# IoT_gateway_ver1A.net
KiCad netlist of a schematic drawn in EasyEDA Pro
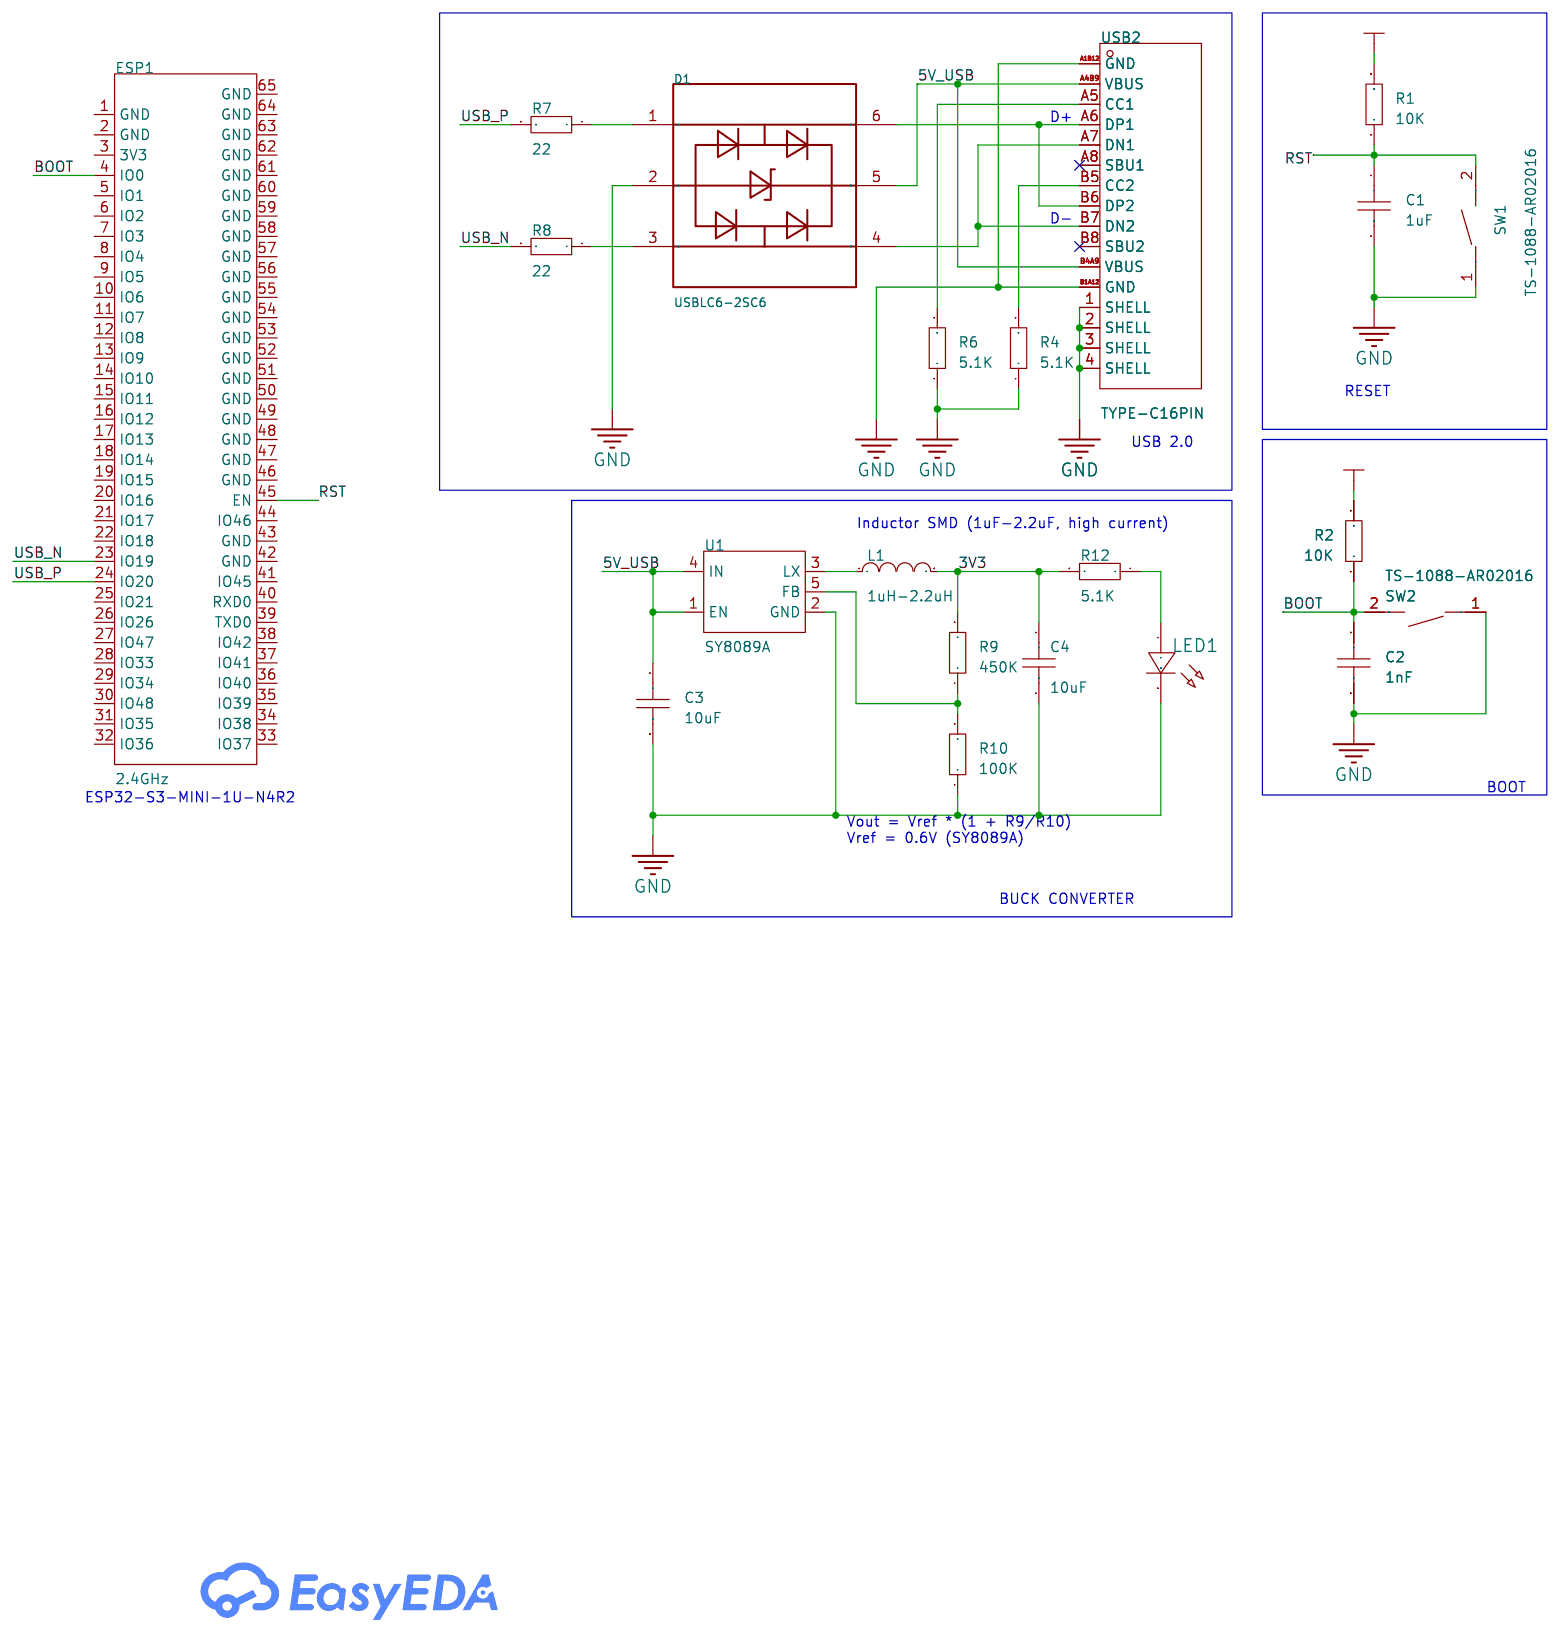
[diagram p0: ESP32-S3-Mini-1U-N4R2]
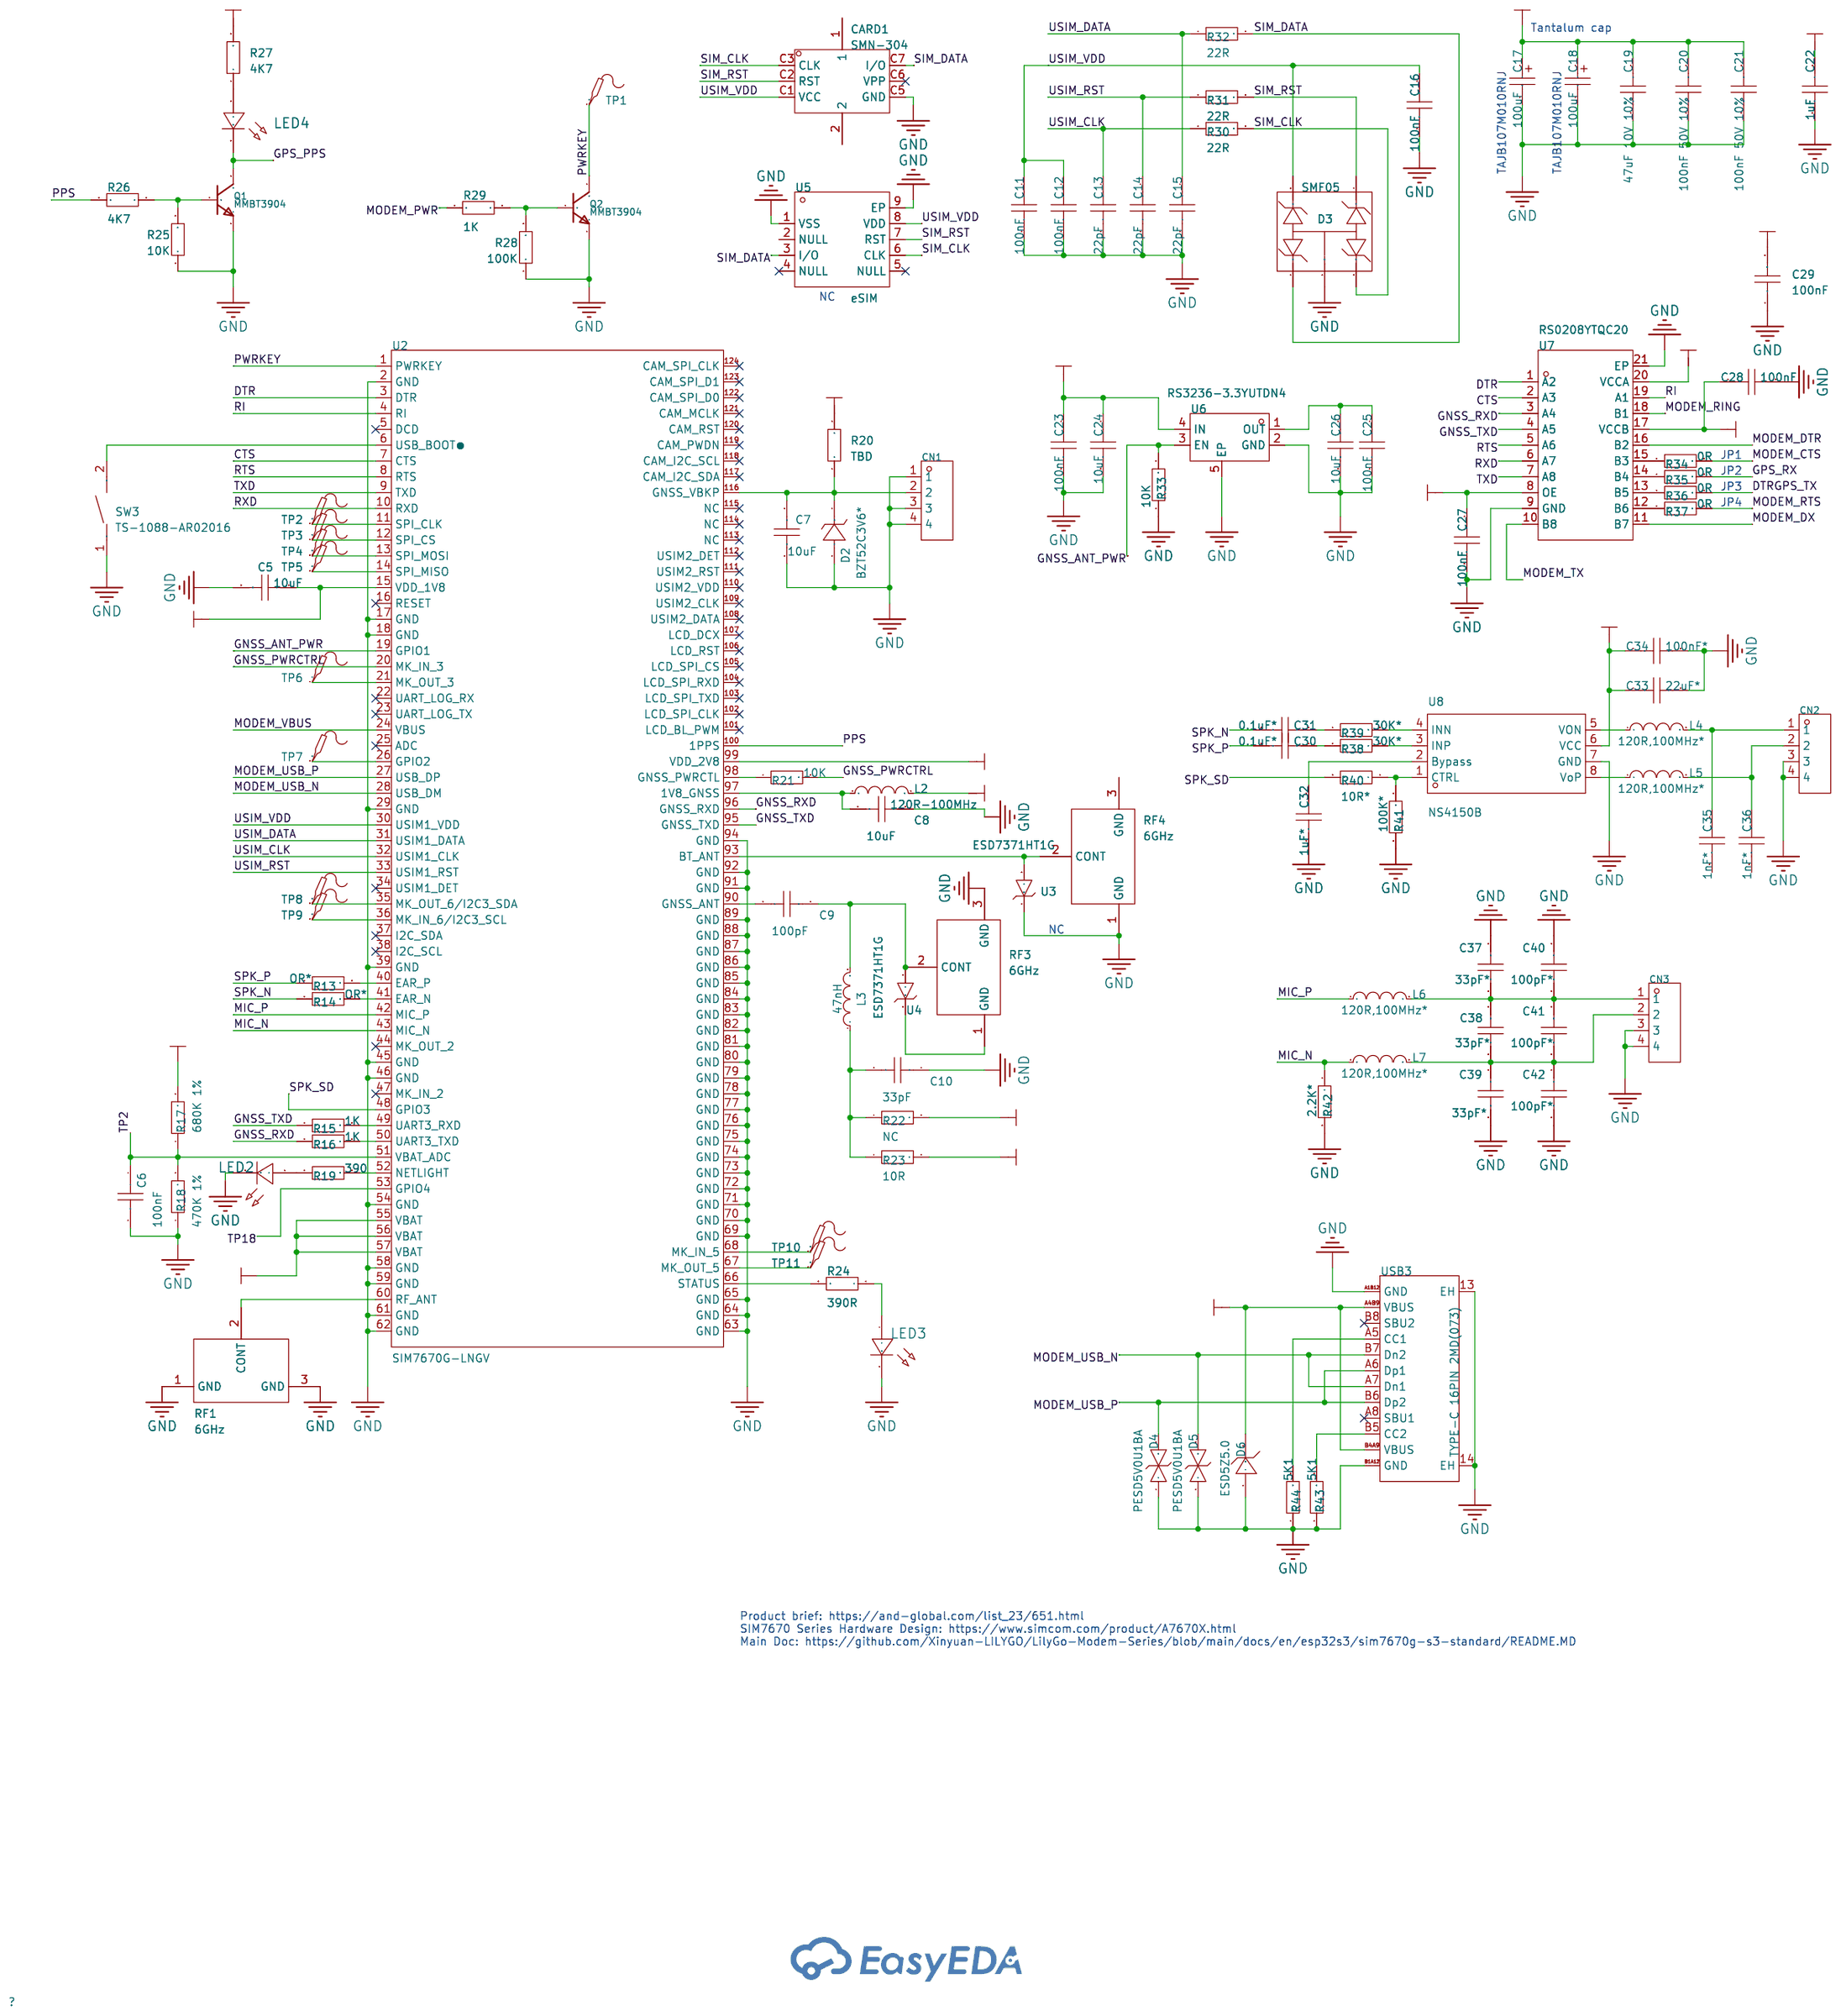
[diagram p1: SIM7670G]
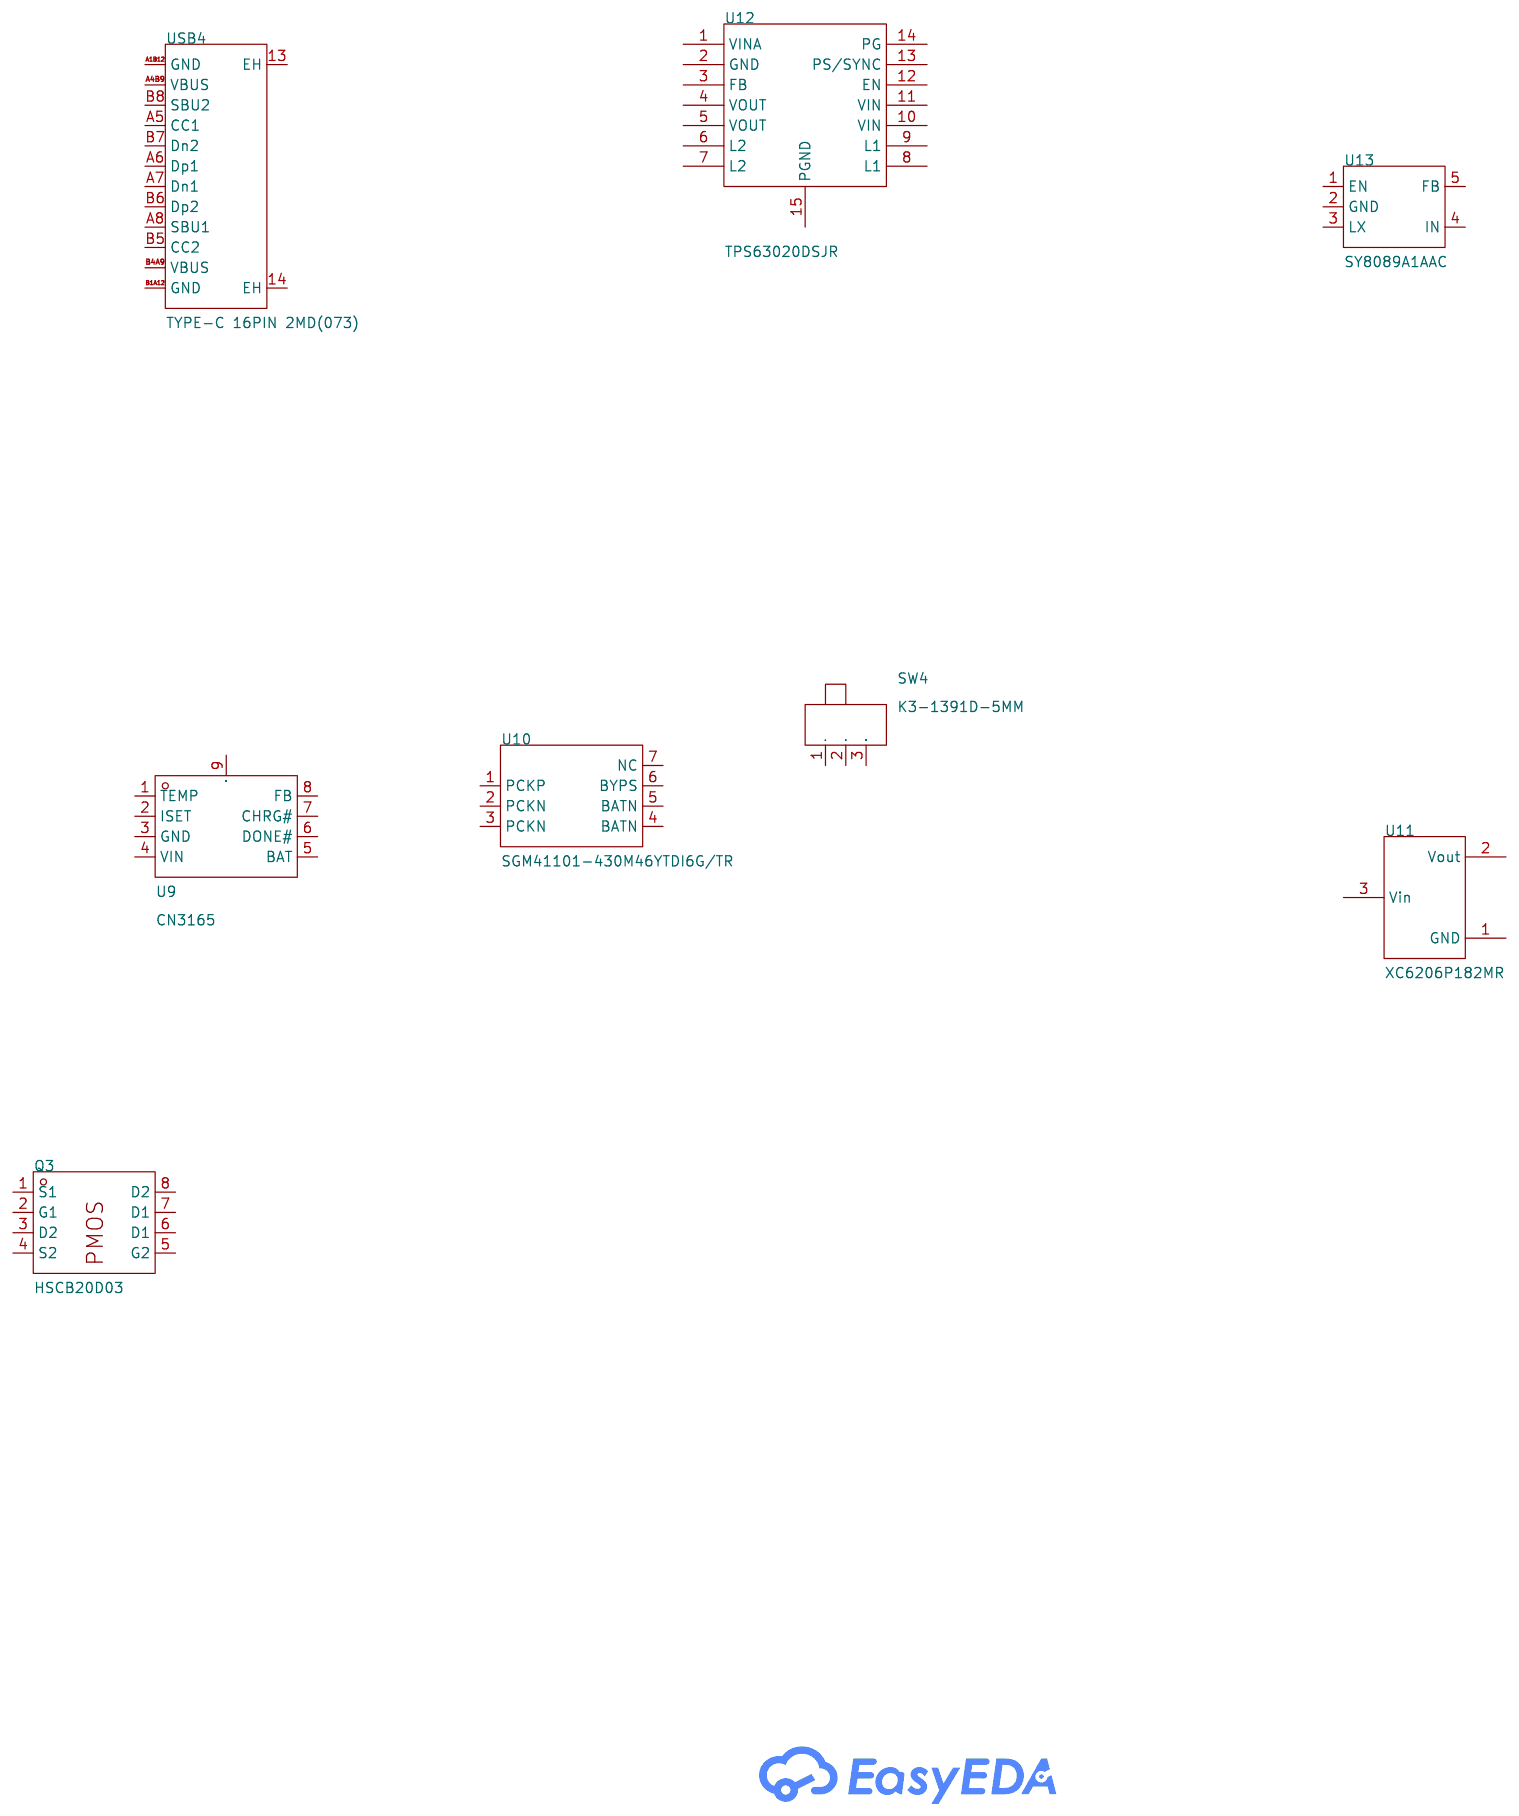
[diagram p2: Power source]
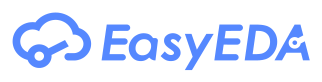
[diagram p3: SX1262]

(export (version "E")
  (design (tool "Eeschema 10.0.6"))
  (components
    (comp (ref "C1")
      (value "1uF")
      (footprint "easyedapro:C0603")
      (libsource (lib "easyedapro") (part "CAP_OLD"))
    )
    (comp (ref "C2")
      (value "1nF")
      (footprint "easyedapro:C0603")
      (libsource (lib "easyedapro") (part "CAP_OLD"))
    )
    (comp (ref "C3")
      (value "10uF")
      (footprint "easyedapro:C0603")
      (libsource (lib "easyedapro") (part "CAP_OLD"))
    )
    (comp (ref "C4")
      (value "10uF")
      (footprint "easyedapro:C0603")
      (libsource (lib "easyedapro") (part "CAP_OLD"))
    )
    (comp (ref "D1")
      (value "USBLC6-2SC6")
      (footprint "easyedapro:TSOT-23-6_L2.9-W1.6-P0.95-LS2.8-BR")
      (fields (field (name "Manufacturer") "Slkor(萨科微)"))
      (libsource (lib "easyedapro") (part "USBLC6-2SC6_C48971164"))
    )
    (comp (ref "ESP1")
      (value "2.4GHz")
      (footprint "easyedapro:BULETM-SMD_ESPRESSIF_ESP32-S3-MINI-1U-N8")
      (fields
        (field (name "Manufacturer Part") "ESP32-S3-MINI-1U-N4R2")
        (field (name "Manufacturer") "ESPRESSIF(乐鑫)")
      )
      (libsource (lib "easyedapro") (part "ESP32-S3-MINI-1U-N4R2"))
    )
    (comp (ref "L1")
      (value "1uH-2.2uH")
      (footprint "easyedapro:L0603")
      (libsource (lib "easyedapro") (part "电感"))
    )
    (comp (ref "LED1")
      (value "~")
      (footprint "easyedapro:LED0402-RD_YELLOW")
      (libsource (lib "easyedapro") (part "LED_R"))
    )
    (comp (ref "R1") (value "10K") (footprint "easyedapro:R0603") (libsource (lib "easyedapro") (part "Res")))
    (comp (ref "R2") (value "10K") (footprint "easyedapro:R0603") (libsource (lib "easyedapro") (part "Res")))
    (comp (ref "R4")
      (value "5.1K")
      (footprint "easyedapro:R0603")
      (libsource (lib "easyedapro") (part "Res"))
    )
    (comp (ref "R6")
      (value "5.1K")
      (footprint "easyedapro:R0603")
      (libsource (lib "easyedapro") (part "Res"))
    )
    (comp (ref "R7") (value "22") (footprint "easyedapro:R0603") (libsource (lib "easyedapro") (part "Res")))
    (comp (ref "R8") (value "22") (footprint "easyedapro:R0603") (libsource (lib "easyedapro") (part "Res")))
    (comp (ref "R9")
      (value "450K")
      (footprint "easyedapro:R0603")
      (libsource (lib "easyedapro") (part "Res"))
    )
    (comp (ref "R10")
      (value "100K")
      (footprint "easyedapro:R0603")
      (libsource (lib "easyedapro") (part "Res"))
    )
    (comp (ref "R12")
      (value "5.1K")
      (footprint "easyedapro:R0603")
      (libsource (lib "easyedapro") (part "Res"))
    )
    (comp (ref "SW1")
      (value "TS-1088-AR02016")
      (footprint "easyedapro:SW-SMD_L3.9-W3.0-P4.45")
      (fields (field (name "Manufacturer") "XUNPU(讯普)"))
      (libsource (lib "easyedapro") (part "TS-1088-AR02016"))
    )
    (comp (ref "SW2")
      (value "TS-1088-AR02016")
      (footprint "easyedapro:SW-SMD_L3.9-W3.0-P4.45")
      (fields (field (name "Manufacturer") "XUNPU(讯普)"))
      (libsource (lib "easyedapro") (part "TS-1088-AR02016"))
    )
    (comp (ref "U1")
      (value "SY8089A")
      (footprint "easyedapro:SOT-23-5_L3.0-W1.7-P0.95-LS2.8-BL")
      (fields (field (name "Manufacturer") "TECH PUBLIC(台舟)"))
      (libsource (lib "easyedapro") (part "SY8089A"))
    )
    (comp (ref "USB2")
      (value "TYPE-C16PIN")
      (footprint "easyedapro:USB-C-SMD_TYPE-C16PIN")
      (fields (field (name "Manufacturer") "SHOU HAN(首韩)"))
      (libsource (lib "easyedapro") (part "TYPE-C16PIN"))
    )
    (comp (ref "C5")
      (value "10uF")
      (footprint "easyedapro:C0603")
      (libsource (lib "easyedapro") (part "CAP_OLD"))
    )
    (comp (ref "C6")
      (value "100nF")
      (footprint "easyedapro:C0603")
      (libsource (lib "easyedapro") (part "CAP_OLD"))
    )
    (comp (ref "C7")
      (value "10uF")
      (footprint "easyedapro:C0603")
      (libsource (lib "easyedapro") (part "CAP_OLD"))
    )
    (comp (ref "C8")
      (value "10uF")
      (footprint "easyedapro:C0603")
      (libsource (lib "easyedapro") (part "CAP_OLD"))
    )
    (comp (ref "C9")
      (value "100pF")
      (footprint "easyedapro:C0603")
      (libsource (lib "easyedapro") (part "CAP_OLD"))
    )
    (comp (ref "C10")
      (value "33pF")
      (footprint "easyedapro:C0603")
      (libsource (lib "easyedapro") (part "CAP_OLD"))
    )
    (comp (ref "C11")
      (value "100nF")
      (footprint "easyedapro:C0603")
      (libsource (lib "easyedapro") (part "CAP_OLD"))
    )
    (comp (ref "C12")
      (value "100nF")
      (footprint "easyedapro:C0603")
      (libsource (lib "easyedapro") (part "CAP_OLD"))
    )
    (comp (ref "C13")
      (value "22pF")
      (footprint "easyedapro:C0603")
      (libsource (lib "easyedapro") (part "CAP_OLD"))
    )
    (comp (ref "C14")
      (value "22pF")
      (footprint "easyedapro:C0603")
      (libsource (lib "easyedapro") (part "CAP_OLD"))
    )
    (comp (ref "C15")
      (value "22pF")
      (footprint "easyedapro:C0603")
      (libsource (lib "easyedapro") (part "CAP_OLD"))
    )
    (comp (ref "C16")
      (value "100nF")
      (footprint "easyedapro:C0603")
      (libsource (lib "easyedapro") (part "CAP_OLD"))
    )
    (comp (ref "C17")
      (value "100uF")
      (footprint "easyedapro:CASE-B_3528")
      (fields (field (name "Manufacturer Part") "TAJB107M010RNJ") (field (name "Manufacturer") "Kyocera AVX"))
      (libsource (lib "easyedapro") (part "TAJB107M010RNJ"))
    )
    (comp (ref "C18")
      (value "100uF")
      (footprint "easyedapro:CASE-B_3528")
      (fields (field (name "Manufacturer Part") "TAJB107M010RNJ") (field (name "Manufacturer") "Kyocera AVX"))
      (libsource (lib "easyedapro") (part "TAJB107M010RNJ"))
    )
    (comp (ref "C19")
      (value "47uF 10V 10%")
      (footprint "easyedapro:C0603")
      (libsource (lib "easyedapro") (part "CAP_OLD"))
    )
    (comp (ref "C20")
      (value "100nF 50V 10%")
      (footprint "easyedapro:C0603")
      (libsource (lib "easyedapro") (part "CAP_OLD"))
    )
    (comp (ref "C21")
      (value "100nF 50V 10%")
      (footprint "easyedapro:C0603")
      (libsource (lib "easyedapro") (part "CAP_OLD"))
    )
    (comp (ref "C22")
      (value "1uF")
      (footprint "easyedapro:C0603")
      (libsource (lib "easyedapro") (part "CAP_OLD"))
    )
    (comp (ref "C23")
      (value "100nF")
      (footprint "easyedapro:C0603")
      (libsource (lib "easyedapro") (part "CAP_OLD"))
    )
    (comp (ref "C24")
      (value "10uF")
      (footprint "easyedapro:C0603")
      (libsource (lib "easyedapro") (part "CAP_OLD"))
    )
    (comp (ref "C25")
      (value "100nF")
      (footprint "easyedapro:C0603")
      (libsource (lib "easyedapro") (part "CAP_OLD"))
    )
    (comp (ref "C26")
      (value "10uF")
      (footprint "easyedapro:C0603")
      (libsource (lib "easyedapro") (part "CAP_OLD"))
    )
    (comp (ref "C27")
      (value "100nF")
      (footprint "easyedapro:C0603")
      (libsource (lib "easyedapro") (part "CAP_OLD"))
    )
    (comp (ref "C28")
      (value "100nF")
      (footprint "easyedapro:C0603")
      (libsource (lib "easyedapro") (part "CAP_OLD"))
    )
    (comp (ref "C29")
      (value "100nF")
      (footprint "easyedapro:C0603")
      (libsource (lib "easyedapro") (part "CAP_OLD"))
    )
    (comp (ref "C30")
      (value "0.1uF*")
      (footprint "easyedapro:C0603")
      (libsource (lib "easyedapro") (part "CAP_OLD"))
    )
    (comp (ref "C31")
      (value "0.1uF*")
      (footprint "easyedapro:C0603")
      (libsource (lib "easyedapro") (part "CAP_OLD"))
    )
    (comp (ref "C32")
      (value "1uF*")
      (footprint "easyedapro:C0603")
      (libsource (lib "easyedapro") (part "CAP_OLD"))
    )
    (comp (ref "C33")
      (value "22uF*")
      (footprint "easyedapro:C0603")
      (libsource (lib "easyedapro") (part "CAP_OLD"))
    )
    (comp (ref "C34")
      (value "100nF*")
      (footprint "easyedapro:C0603")
      (libsource (lib "easyedapro") (part "CAP_OLD"))
    )
    (comp (ref "C35")
      (value "1nF*")
      (footprint "easyedapro:C0603")
      (libsource (lib "easyedapro") (part "CAP_OLD"))
    )
    (comp (ref "C36")
      (value "1nF*")
      (footprint "easyedapro:C0603")
      (libsource (lib "easyedapro") (part "CAP_OLD"))
    )
    (comp (ref "C37")
      (value "33pF*")
      (footprint "easyedapro:C0603")
      (libsource (lib "easyedapro") (part "CAP_OLD"))
    )
    (comp (ref "C38")
      (value "33pF*")
      (footprint "easyedapro:C0603")
      (libsource (lib "easyedapro") (part "CAP_OLD"))
    )
    (comp (ref "C39")
      (value "33pF*")
      (footprint "easyedapro:C0603")
      (libsource (lib "easyedapro") (part "CAP_OLD"))
    )
    (comp (ref "C40")
      (value "100pF*")
      (footprint "easyedapro:C0603")
      (libsource (lib "easyedapro") (part "CAP_OLD"))
    )
    (comp (ref "C41")
      (value "100pF*")
      (footprint "easyedapro:C0603")
      (libsource (lib "easyedapro") (part "CAP_OLD"))
    )
    (comp (ref "C42")
      (value "100pF*")
      (footprint "easyedapro:C0603")
      (libsource (lib "easyedapro") (part "CAP_OLD"))
    )
    (comp (ref "CARD1")
      (value "SMN-304")
      (footprint "easyedapro:SIM-SMD_SMN-304")
      (fields (field (name "Manufacturer") "XUNPU(讯普)"))
      (libsource (lib "easyedapro") (part "SMN-304"))
    )
    (comp (ref "CN1")
      (value "~")
      (footprint "easyedapro:HDR-TH_4P-P2.54-V-F")
      (libsource (lib "easyedapro") (part "2.54-1*4P母"))
    )
    (comp (ref "CN2")
      (value "~")
      (footprint "easyedapro:HDR-TH_4P-P2.54-V-F")
      (libsource (lib "easyedapro") (part "2.54-1*4P母"))
    )
    (comp (ref "CN3")
      (value "~")
      (footprint "easyedapro:HDR-TH_4P-P2.54-V-F")
      (libsource (lib "easyedapro") (part "2.54-1*4P母"))
    )
    (comp (ref "D2")
      (value "BZT52C3V6*")
      (footprint "easyedapro:SOD-123_L2.8-W1.8-LS3.7-RD")
      (fields (field (name "Manufacturer") "PAKER(派克微)"))
      (libsource (lib "easyedapro") (part "BZT52C3V6_C49652771"))
    )
    (comp (ref "D3")
      (value "SMF05")
      (footprint "easyedapro:SOT-353_L2.0-W1.2-P0.65-LS2.1-BL-1")
      (fields (field (name "Manufacturer") "WPMtek(维攀)"))
      (libsource (lib "easyedapro") (part "SMF05"))
    )
    (comp (ref "D4")
      (value "PESD5V0U1BA")
      (footprint "easyedapro:SOD-323_L1.8-W1.3-LS2.5-BI")
      (fields (field (name "Manufacturer") "UMW(友台半导体)"))
      (libsource (lib "easyedapro") (part "PESD5V0U1BA_C5199862"))
    )
    (comp (ref "D5")
      (value "PESD5V0U1BA")
      (footprint "easyedapro:SOD-323_L1.8-W1.3-LS2.5-BI")
      (fields (field (name "Manufacturer") "UMW(友台半导体)"))
      (libsource (lib "easyedapro") (part "PESD5V0U1BA_C5199862"))
    )
    (comp (ref "D6")
      (value "ESD5Z5.0")
      (footprint "easyedapro:SOD-523_L1.2-W0.8-LS1.6-RD")
      (fields (field (name "Manufacturer") "AnBon(安邦)"))
      (libsource (lib "easyedapro") (part "ESD5Z5.0"))
    )
    (comp (ref "L2")
      (value "120R-100MHz")
      (footprint "easyedapro:L0603")
      (libsource (lib "easyedapro") (part "电感"))
    )
    (comp (ref "L3") (value "47nH") (footprint "easyedapro:L0603") (libsource (lib "easyedapro") (part "电感")))
    (comp (ref "L4")
      (value "120R,100MHz*")
      (footprint "easyedapro:L0603")
      (libsource (lib "easyedapro") (part "电感"))
    )
    (comp (ref "L5")
      (value "120R,100MHz*")
      (footprint "easyedapro:L0603")
      (libsource (lib "easyedapro") (part "电感"))
    )
    (comp (ref "L6")
      (value "120R,100MHz*")
      (footprint "easyedapro:L0603")
      (libsource (lib "easyedapro") (part "电感"))
    )
    (comp (ref "L7")
      (value "120R,100MHz*")
      (footprint "easyedapro:L0603")
      (libsource (lib "easyedapro") (part "电感"))
    )
    (comp (ref "LED2")
      (value "~")
      (footprint "easyedapro:LED0402-RD_YELLOW")
      (libsource (lib "easyedapro") (part "LED_R"))
    )
    (comp (ref "LED3")
      (value "~")
      (footprint "easyedapro:LED0402-RD_YELLOW")
      (libsource (lib "easyedapro") (part "LED_R"))
    )
    (comp (ref "LED4")
      (value "~")
      (footprint "easyedapro:LED0402-RD_YELLOW")
      (libsource (lib "easyedapro") (part "LED_R"))
    )
    (comp (ref "Q1")
      (value "MMBT3904")
      (footprint "easyedapro:SOT-23-3_L3.0-W1.7-P0.95-LS2.9-BR")
      (fields (field (name "Manufacturer") "ALJ(龙晶微)"))
      (libsource (lib "easyedapro") (part "MMBT3904_C55258612"))
    )
    (comp (ref "Q2")
      (value "MMBT3904")
      (footprint "easyedapro:SOT-23-3_L3.0-W1.7-P0.95-LS2.9-BR")
      (fields (field (name "Manufacturer") "ALJ(龙晶微)"))
      (libsource (lib "easyedapro") (part "MMBT3904_C55258612"))
    )
    (comp (ref "R13")
      (value "OR*")
      (footprint "easyedapro:R0603")
      (libsource (lib "easyedapro") (part "Res"))
    )
    (comp (ref "R14")
      (value "OR*")
      (footprint "easyedapro:R0603")
      (libsource (lib "easyedapro") (part "Res"))
    )
    (comp (ref "R15") (value "1K") (footprint "easyedapro:R0603") (libsource (lib "easyedapro") (part "Res")))
    (comp (ref "R16") (value "1K") (footprint "easyedapro:R0603") (libsource (lib "easyedapro") (part "Res")))
    (comp (ref "R17")
      (value "680K 1%")
      (footprint "easyedapro:R0603")
      (libsource (lib "easyedapro") (part "Res"))
    )
    (comp (ref "R18")
      (value "470K 1%")
      (footprint "easyedapro:R0603")
      (libsource (lib "easyedapro") (part "Res"))
    )
    (comp (ref "R19")
      (value "390")
      (footprint "easyedapro:R0603")
      (libsource (lib "easyedapro") (part "Res"))
    )
    (comp (ref "R20")
      (value "TBD")
      (footprint "easyedapro:R0603")
      (libsource (lib "easyedapro") (part "Res"))
    )
    (comp (ref "R21")
      (value "10K")
      (footprint "easyedapro:R0603")
      (libsource (lib "easyedapro") (part "Res"))
    )
    (comp (ref "R22") (value "NC") (footprint "easyedapro:R0603") (libsource (lib "easyedapro") (part "Res")))
    (comp (ref "R23")
      (value "10R")
      (footprint "easyedapro:R0603")
      (libsource (lib "easyedapro") (part "Res"))
    )
    (comp (ref "R24")
      (value "390R")
      (footprint "easyedapro:R0603")
      (libsource (lib "easyedapro") (part "Res"))
    )
    (comp (ref "R25")
      (value "10K")
      (footprint "easyedapro:R0603")
      (libsource (lib "easyedapro") (part "Res"))
    )
    (comp (ref "R26")
      (value "4K7")
      (footprint "easyedapro:R0603")
      (libsource (lib "easyedapro") (part "Res"))
    )
    (comp (ref "R27")
      (value "4K7")
      (footprint "easyedapro:R0603")
      (libsource (lib "easyedapro") (part "Res"))
    )
    (comp (ref "R28")
      (value "100K")
      (footprint "easyedapro:R0603")
      (libsource (lib "easyedapro") (part "Res"))
    )
    (comp (ref "R29") (value "1K") (footprint "easyedapro:R0603") (libsource (lib "easyedapro") (part "Res")))
    (comp (ref "R30")
      (value "22R")
      (footprint "easyedapro:R0603")
      (libsource (lib "easyedapro") (part "Res"))
    )
    (comp (ref "R31")
      (value "22R")
      (footprint "easyedapro:R0603")
      (libsource (lib "easyedapro") (part "Res"))
    )
    (comp (ref "R32")
      (value "22R")
      (footprint "easyedapro:R0603")
      (libsource (lib "easyedapro") (part "Res"))
    )
    (comp (ref "R33")
      (value "10K")
      (footprint "easyedapro:R0603")
      (libsource (lib "easyedapro") (part "Res"))
    )
    (comp (ref "R34") (value "0R") (footprint "easyedapro:R0603") (libsource (lib "easyedapro") (part "Res")))
    (comp (ref "R35") (value "0R") (footprint "easyedapro:R0603") (libsource (lib "easyedapro") (part "Res")))
    (comp (ref "R36") (value "0R") (footprint "easyedapro:R0603") (libsource (lib "easyedapro") (part "Res")))
    (comp (ref "R37") (value "0R") (footprint "easyedapro:R0603") (libsource (lib "easyedapro") (part "Res")))
    (comp (ref "R38")
      (value "30K*")
      (footprint "easyedapro:R0603")
      (libsource (lib "easyedapro") (part "Res"))
    )
    (comp (ref "R39")
      (value "30K*")
      (footprint "easyedapro:R0603")
      (libsource (lib "easyedapro") (part "Res"))
    )
    (comp (ref "R40")
      (value "10R*")
      (footprint "easyedapro:R0603")
      (libsource (lib "easyedapro") (part "Res"))
    )
    (comp (ref "R41")
      (value "100K*")
      (footprint "easyedapro:R0603")
      (libsource (lib "easyedapro") (part "Res"))
    )
    (comp (ref "R42")
      (value "2.2K*")
      (footprint "easyedapro:R0603")
      (libsource (lib "easyedapro") (part "Res"))
    )
    (comp (ref "R43")
      (value "5K1")
      (footprint "easyedapro:R0603")
      (libsource (lib "easyedapro") (part "Res"))
    )
    (comp (ref "R44")
      (value "5K1")
      (footprint "easyedapro:R0603")
      (libsource (lib "easyedapro") (part "Res"))
    )
    (comp (ref "RF1")
      (value "6GHz")
      (footprint "easyedapro:ANT-SMD_UFL-R-SMT01")
      (fields (field (name "Manufacturer Part") "U.FL-R-SMT(01)") (field (name "Manufacturer") "HRS(广濑)"))
      (libsource (lib "easyedapro") (part "U.FL-R-SMT(01)"))
    )
    (comp (ref "RF3")
      (value "6GHz")
      (footprint "easyedapro:ANT-SMD_UFL-R-SMT01")
      (fields (field (name "Manufacturer Part") "U.FL-R-SMT(01)") (field (name "Manufacturer") "HRS(广濑)"))
      (libsource (lib "easyedapro") (part "U.FL-R-SMT(01)"))
    )
    (comp (ref "RF4")
      (value "6GHz")
      (footprint "easyedapro:ANT-SMD_UFL-R-SMT01")
      (fields (field (name "Manufacturer Part") "U.FL-R-SMT(01)") (field (name "Manufacturer") "HRS(广濑)"))
      (libsource (lib "easyedapro") (part "U.FL-R-SMT(01)"))
    )
    (comp (ref "SW3")
      (value "TS-1088-AR02016")
      (footprint "easyedapro:SW-SMD_L3.9-W3.0-P4.45")
      (fields (field (name "Manufacturer") "XUNPU(讯普)"))
      (libsource (lib "easyedapro") (part "TS-1088-AR02016"))
    )
    (comp (ref "TP1")
      (value "~")
      (footprint "easyedapro:Test-Point-0.5mm")
      (description "Test Point 测试点")
      (libsource (lib "easyedapro") (part "Test-Point"))
    )
    (comp (ref "TP2")
      (value "~")
      (footprint "easyedapro:Test-Point-0.5mm")
      (description "Test Point 测试点")
      (libsource (lib "easyedapro") (part "Test-Point"))
    )
    (comp (ref "TP3")
      (value "~")
      (footprint "easyedapro:Test-Point-0.5mm")
      (description "Test Point 测试点")
      (libsource (lib "easyedapro") (part "Test-Point"))
    )
    (comp (ref "TP4")
      (value "~")
      (footprint "easyedapro:Test-Point-0.5mm")
      (description "Test Point 测试点")
      (libsource (lib "easyedapro") (part "Test-Point"))
    )
    (comp (ref "TP5")
      (value "~")
      (footprint "easyedapro:Test-Point-0.5mm")
      (description "Test Point 测试点")
      (libsource (lib "easyedapro") (part "Test-Point"))
    )
    (comp (ref "TP6")
      (value "~")
      (footprint "easyedapro:Test-Point-0.5mm")
      (description "Test Point 测试点")
      (libsource (lib "easyedapro") (part "Test-Point"))
    )
    (comp (ref "TP7")
      (value "~")
      (footprint "easyedapro:Test-Point-0.5mm")
      (description "Test Point 测试点")
      (libsource (lib "easyedapro") (part "Test-Point"))
    )
    (comp (ref "TP8")
      (value "~")
      (footprint "easyedapro:Test-Point-0.5mm")
      (description "Test Point 测试点")
      (libsource (lib "easyedapro") (part "Test-Point"))
    )
    (comp (ref "TP9")
      (value "~")
      (footprint "easyedapro:Test-Point-0.5mm")
      (description "Test Point 测试点")
      (libsource (lib "easyedapro") (part "Test-Point"))
    )
    (comp (ref "TP10")
      (value "~")
      (footprint "easyedapro:Test-Point-0.5mm")
      (description "Test Point 测试点")
      (libsource (lib "easyedapro") (part "Test-Point"))
    )
    (comp (ref "TP11")
      (value "~")
      (footprint "easyedapro:Test-Point-0.5mm")
      (description "Test Point 测试点")
      (libsource (lib "easyedapro") (part "Test-Point"))
    )
    (comp (ref "U2")
      (value "SIM7670G-LNGV")
      (footprint "easyedapro:LCC-124_L24.0-W24.0-P1.0-TL")
      (fields (field (name "Manufacturer") "SIMCOM(芯讯通无线科技)"))
      (libsource (lib "easyedapro") (part "SIM7670G-LNGV"))
    )
    (comp (ref "U3")
      (value "ESD7371HT1G")
      (footprint "easyedapro:SOD-323_L1.7-W1.3-LS2.5-RD")
      (fields (field (name "Manufacturer") "onsemi(安森美)"))
      (libsource (lib "easyedapro") (part "ESD7371HT1G"))
    )
    (comp (ref "U4")
      (value "ESD7371HT1G")
      (footprint "easyedapro:SOD-323_L1.7-W1.3-LS2.5-RD")
      (fields (field (name "Manufacturer") "onsemi(安森美)"))
      (libsource (lib "easyedapro") (part "ESD7371HT1G"))
    )
    (comp (ref "U5")
      (value "eSIM")
      (footprint "easyedapro:DFN-8_L2.0-W2.0-P0.50-LS2.0-BL-EP")
      (libsource (lib "easyedapro") (part "ESIM_C9900092443"))
    )
    (comp (ref "U6")
      (value "RS3236-3.3YUTDN4")
      (footprint "easyedapro:XDFN-4_L1.0-W1.0-P0.65-BL-EP")
      (fields (field (name "Manufacturer") "RUNIC(润石)"))
      (libsource (lib "easyedapro") (part "RS3236-3.3YUTDN4"))
    )
    (comp (ref "U7")
      (value "RS0208YTQC20")
      (footprint "easyedapro:QFN-20_L3.0-W3.0-P0.40-BL-EP1.7")
      (fields (field (name "Manufacturer") "RUNIC(润石)"))
      (libsource (lib "easyedapro") (part "RS0208YTQC20"))
    )
    (comp (ref "U8")
      (value "NS4150B")
      (footprint "easyedapro:MSOP-8_L3.0-W3.0-P0.65-LS5.0-BL")
      (description "Class:Class D Output Power:3Wx1@4Ω Voltage - Supply:3V~5.25V Voltage - Supply:3V~5.25V")
      (fields (field (name "Manufacturer") "Nsiway(纳芯威)"))
      (libsource (lib "easyedapro") (part "NS4150"))
    )
    (comp (ref "USB3")
      (value "TYPE-C 16PIN 2MD(073)")
      (footprint "easyedapro:USB-C-SMD_TYPE-C-16PIN-2MD-073")
      (fields (field (name "Manufacturer") "SHOU HAN(首韩)"))
      (libsource (lib "easyedapro") (part "TYPE-C 16PIN 2MD(073)"))
    )
    (comp (ref "Q3")
      (value "HSCB20D03")
      (footprint "easyedapro:DFN-6_L2.0-W2.0-P0.65-BL-EP2")
      (fields (field (name "Manufacturer") "HUASHUO(华朔)"))
      (libsource (lib "easyedapro") (part "HSCB20D03"))
    )
    (comp (ref "SW4")
      (value "K3-1391D-5MM")
      (footprint "easyedapro:SW-TH_K3-1391D-5MM")
      (fields (field (name "Manufacturer") "韩国韩荣"))
      (libsource (lib "easyedapro") (part "K3-1391D-5MM"))
    )
    (comp (ref "U9")
      (value "CN3165")
      (footprint "easyedapro:DFN-8_L3.0-W3.0-P0.50-BL-EP")
      (fields (field (name "Manufacturer") "CONSONANCE(上海如韵)"))
      (libsource (lib "easyedapro") (part "CN3165"))
    )
    (comp (ref "U10")
      (value "SGM41101-430M46YTDI6G/TR")
      (footprint "easyedapro:TDFN-6_L2.0-W2.0-P0.65-TL-EP1.4")
      (fields (field (name "Manufacturer") "SGMICRO(圣邦微)"))
      (libsource (lib "easyedapro") (part "SGM41101-430M46YTDI6G/TR"))
    )
    (comp (ref "U11")
      (value "XC6206P182MR")
      (footprint "easyedapro:SOT-23-3_L2.9-W1.6-P1.90-LS2.8-BR")
      (fields (field (name "Manufacturer") "TECH PUBLIC(台舟)"))
      (libsource (lib "easyedapro") (part "XC6206P182MR_C51886219"))
    )
    (comp (ref "U12")
      (value "TPS63020DSJR")
      (footprint "easyedapro:VSON-14_L4.0-W3.0-P0.50-BL-EP_TI_DSJ")
      (fields (field (name "Manufacturer") "TI(德州仪器)"))
      (libsource (lib "easyedapro") (part "TPS63020DSJR"))
    )
    (comp (ref "U13")
      (value "SY8089A1AAC")
      (footprint "easyedapro:TSOT-23-5_L2.9-W1.6-P0.95-LS2.8-BR")
      (fields (field (name "Manufacturer") "Silergy(矽力杰)"))
      (libsource (lib "easyedapro") (part "SY8089A1AAC"))
    )
    (comp (ref "USB4")
      (value "TYPE-C 16PIN 2MD(073)")
      (footprint "easyedapro:USB-C-SMD_TYPE-C-16PIN-2MD-073")
      (fields (field (name "Manufacturer") "SHOU HAN(首韩)"))
      (libsource (lib "easyedapro") (part "TYPE-C 16PIN 2MD(073)"))
    )
  )
  (nets
    (net (code "1") (name "+1.8V") (class "Default")
      (node (ref "C5") (pin "1") (pinfunction "1_1") (pintype "input"))
      (node (ref "U2") (pin "15") (pinfunction "VDD_1V8_15") (pintype "unspecified"))
    )
    (net (code "2") (name "+1V8") (class "Default")
      (node (ref "C27") (pin "1") (pinfunction "1_1") (pintype "input"))
      (node (ref "C29") (pin "2") (pinfunction "2_2") (pintype "input"))
      (node (ref "L2") (pin "2") (pinfunction "2_2") (pintype "input"))
      (node (ref "U7") (pin "20") (pinfunction "VCCA_20") (pintype "unspecified"))
      (node (ref "U7") (pin "8") (pinfunction "OE_8") (pintype "unspecified"))
    )
    (net (code "3") (name "+3V3") (class "Default")
      (node (ref "C28") (pin "1") (pinfunction "1_1") (pintype "input"))
      (node (ref "R27") (pin "2") (pinfunction "2_2") (pintype "input"))
      (node (ref "U7") (pin "17") (pinfunction "VCCB_17") (pintype "unspecified"))
    )
    (net (code "4") (name "+3V6") (class "Default")
      (node (ref "C17") (pin "1") (pinfunction "1_1") (pintype "input"))
      (node (ref "C18") (pin "1") (pinfunction "1_1") (pintype "input"))
      (node (ref "C19") (pin "1") (pinfunction "1_1") (pintype "input"))
      (node (ref "C20") (pin "1") (pinfunction "1_1") (pintype "input"))
      (node (ref "C21") (pin "1") (pinfunction "1_1") (pintype "input"))
      (node (ref "C23") (pin "1") (pinfunction "1_1") (pintype "input"))
      (node (ref "C24") (pin "1") (pinfunction "1_1") (pintype "input"))
      (node (ref "C33") (pin "1") (pinfunction "1_1") (pintype "input"))
      (node (ref "C34") (pin "1") (pinfunction "1_1") (pintype "input"))
      (node (ref "U2") (pin "55") (pinfunction "VBAT_55") (pintype "unspecified"))
      (node (ref "U2") (pin "56") (pinfunction "VBAT_56") (pintype "unspecified"))
      (node (ref "U2") (pin "57") (pinfunction "VBAT_57") (pintype "unspecified"))
      (node (ref "U6") (pin "4") (pinfunction "IN_4") (pintype "unspecified"))
      (node (ref "U8") (pin "6") (pinfunction "VCC_6") (pintype "unspecified"))
    )
    (net (code "5") (name "3.3V") (class "Default")
      (node (ref "R1") (pin "2") (pinfunction "2_2") (pintype "input"))
      (node (ref "R2") (pin "2") (pinfunction "2_2") (pintype "input"))
    )
    (net (code "6") (name "3V3") (class "Default")
      (node (ref "C4") (pin "1") (pinfunction "1_1") (pintype "input"))
      (node (ref "L1") (pin "2") (pinfunction "2_2") (pintype "input"))
      (node (ref "R12") (pin "2") (pinfunction "2_2") (pintype "input"))
      (node (ref "R9") (pin "2") (pinfunction "2_2") (pintype "input"))
    )
    (net (code "7") (name "5V_USB") (class "Default")
      (node (ref "C3") (pin "1") (pinfunction "1_1") (pintype "input"))
      (node (ref "D1") (pin "5") (pinfunction "VBUS_5") (pintype "input"))
      (node (ref "U1") (pin "1") (pinfunction "EN_1") (pintype "unspecified"))
      (node (ref "U1") (pin "4") (pinfunction "IN_4") (pintype "unspecified"))
      (node (ref "USB2") (pin "A4B9") (pinfunction "VBUS_A4B9") (pintype "unspecified"))
      (node (ref "USB2") (pin "B4A9") (pinfunction "VBUS_B4A9") (pintype "unspecified"))
    )
    (net (code "8") (name "BOOT") (class "Default")
      (node (ref "C2") (pin "1") (pinfunction "1_1") (pintype "input"))
      (node (ref "ESP1") (pin "4") (pinfunction "IO0_4") (pintype "unspecified"))
      (node (ref "R2") (pin "1") (pinfunction "1_1") (pintype "input"))
      (node (ref "SW2") (pin "2") (pinfunction "2_2") (pintype "unspecified"))
    )
    (net (code "9") (name "CTS") (class "Default")
      (node (ref "U2") (pin "7") (pinfunction "CTS_7") (pintype "unspecified"))
      (node (ref "U7") (pin "2") (pinfunction "A3_2") (pintype "unspecified"))
    )
    (net (code "10") (name "DTR") (class "Default")
      (node (ref "U2") (pin "3") (pinfunction "DTR_3") (pintype "unspecified"))
      (node (ref "U7") (pin "1") (pinfunction "A2_1") (pintype "unspecified"))
    )
    (net (code "11") (name "DTRGPS_TX") (class "Default")
      (node (ref "R36") (pin "2") (pinfunction "2_2") (pintype "input"))
    )
    (net (code "12") (name "GND") (class "Default")
      (node (ref "C1") (pin "2") (pinfunction "2_2") (pintype "input"))
      (node (ref "C10") (pin "1") (pinfunction "1_1") (pintype "input"))
      (node (ref "C11") (pin "2") (pinfunction "2_2") (pintype "input"))
      (node (ref "C12") (pin "2") (pinfunction "2_2") (pintype "input"))
      (node (ref "C13") (pin "2") (pinfunction "2_2") (pintype "input"))
      (node (ref "C14") (pin "2") (pinfunction "2_2") (pintype "input"))
      (node (ref "C15") (pin "2") (pinfunction "2_2") (pintype "input"))
      (node (ref "C16") (pin "2") (pinfunction "2_2") (pintype "input"))
      (node (ref "C17") (pin "2") (pinfunction "2_2") (pintype "input"))
      (node (ref "C18") (pin "2") (pinfunction "2_2") (pintype "input"))
      (node (ref "C19") (pin "2") (pinfunction "2_2") (pintype "input"))
      (node (ref "C2") (pin "2") (pinfunction "2_2") (pintype "input"))
      (node (ref "C20") (pin "2") (pinfunction "2_2") (pintype "input"))
      (node (ref "C21") (pin "2") (pinfunction "2_2") (pintype "input"))
      (node (ref "C22") (pin "2") (pinfunction "2_2") (pintype "input"))
      (node (ref "C23") (pin "2") (pinfunction "2_2") (pintype "input"))
      (node (ref "C24") (pin "2") (pinfunction "2_2") (pintype "input"))
      (node (ref "C25") (pin "2") (pinfunction "2_2") (pintype "input"))
      (node (ref "C26") (pin "2") (pinfunction "2_2") (pintype "input"))
      (node (ref "C27") (pin "2") (pinfunction "2_2") (pintype "input"))
      (node (ref "C28") (pin "2") (pinfunction "2_2") (pintype "input"))
      (node (ref "C29") (pin "1") (pinfunction "1_1") (pintype "input"))
      (node (ref "C3") (pin "2") (pinfunction "2_2") (pintype "input"))
      (node (ref "C32") (pin "2") (pinfunction "2_2") (pintype "input"))
      (node (ref "C33") (pin "2") (pinfunction "2_2") (pintype "input"))
      (node (ref "C34") (pin "2") (pinfunction "2_2") (pintype "input"))
      (node (ref "C37") (pin "1") (pinfunction "1_1") (pintype "input"))
      (node (ref "C39") (pin "2") (pinfunction "2_2") (pintype "input"))
      (node (ref "C4") (pin "2") (pinfunction "2_2") (pintype "input"))
      (node (ref "C40") (pin "1") (pinfunction "1_1") (pintype "input"))
      (node (ref "C42") (pin "2") (pinfunction "2_2") (pintype "input"))
      (node (ref "C5") (pin "2") (pinfunction "2_2") (pintype "input"))
      (node (ref "C6") (pin "2") (pinfunction "2_2") (pintype "input"))
      (node (ref "C7") (pin "2") (pinfunction "2_2") (pintype "input"))
      (node (ref "C8") (pin "1") (pinfunction "1_1") (pintype "input"))
      (node (ref "CARD1") (pin "C5") (pinfunction "GND_C5") (pintype "unspecified"))
      (node (ref "CN1") (pin "1") (pinfunction "1_1") (pintype "input"))
      (node (ref "CN1") (pin "3") (pinfunction "3_3") (pintype "input"))
      (node (ref "CN1") (pin "4") (pinfunction "4_4") (pintype "input"))
      (node (ref "CN2") (pin "3") (pinfunction "3_3") (pintype "input"))
      (node (ref "CN2") (pin "4") (pinfunction "4_4") (pintype "input"))
      (node (ref "CN3") (pin "3") (pinfunction "3_3") (pintype "input"))
      (node (ref "CN3") (pin "4") (pinfunction "4_4") (pintype "input"))
      (node (ref "D1") (pin "2") (pinfunction "GND_2") (pintype "input"))
      (node (ref "D2") (pin "2") (pinfunction "A_2") (pintype "unspecified"))
      (node (ref "D3") (pin "2") (pinfunction "2_2") (pintype "unspecified"))
      (node (ref "D4") (pin "1") (pinfunction "1_1") (pintype "unspecified"))
      (node (ref "D5") (pin "1") (pinfunction "1_1") (pintype "unspecified"))
      (node (ref "D6") (pin "2") (pinfunction "A_2") (pintype "unspecified"))
      (node (ref "LED1") (pin "2") (pinfunction "C_2") (pintype "input"))
      (node (ref "LED2") (pin "2") (pinfunction "C_2") (pintype "input"))
      (node (ref "LED3") (pin "2") (pinfunction "C_2") (pintype "input"))
      (node (ref "Q1") (pin "2") (pinfunction "E_2") (pintype "input"))
      (node (ref "Q2") (pin "2") (pinfunction "E_2") (pintype "input"))
      (node (ref "R10") (pin "1") (pinfunction "1_1") (pintype "input"))
      (node (ref "R18") (pin "1") (pinfunction "1_1") (pintype "input"))
      (node (ref "R25") (pin "1") (pinfunction "1_1") (pintype "input"))
      (node (ref "R28") (pin "1") (pinfunction "1_1") (pintype "input"))
      (node (ref "R33") (pin "1") (pinfunction "1_1") (pintype "input"))
      (node (ref "R4") (pin "1") (pinfunction "1_1") (pintype "input"))
      (node (ref "R41") (pin "2") (pinfunction "2_2") (pintype "input"))
      (node (ref "R42") (pin "2") (pinfunction "2_2") (pintype "input"))
      (node (ref "R43") (pin "1") (pinfunction "1_1") (pintype "input"))
      (node (ref "R44") (pin "1") (pinfunction "1_1") (pintype "input"))
      (node (ref "R6") (pin "1") (pinfunction "1_1") (pintype "input"))
      (node (ref "RF1") (pin "1") (pinfunction "GND_1") (pintype "unspecified"))
      (node (ref "RF1") (pin "3") (pinfunction "GND_3") (pintype "unspecified"))
      (node (ref "RF3") (pin "3") (pinfunction "GND_3") (pintype "unspecified"))
      (node (ref "RF4") (pin "1") (pinfunction "GND_1") (pintype "unspecified"))
      (node (ref "SW1") (pin "1") (pinfunction "1_1") (pintype "unspecified"))
      (node (ref "SW2") (pin "1") (pinfunction "1_1") (pintype "unspecified"))
      (node (ref "SW3") (pin "1") (pinfunction "1_1") (pintype "unspecified"))
      (node (ref "U1") (pin "2") (pinfunction "GND_2") (pintype "unspecified"))
      (node (ref "U2") (pin "17") (pinfunction "GND_17") (pintype "unspecified"))
      (node (ref "U2") (pin "18") (pinfunction "GND_18") (pintype "unspecified"))
      (node (ref "U2") (pin "2") (pinfunction "GND_2") (pintype "unspecified"))
      (node (ref "U2") (pin "29") (pinfunction "GND_29") (pintype "unspecified"))
      (node (ref "U2") (pin "39") (pinfunction "GND_39") (pintype "unspecified"))
      (node (ref "U2") (pin "45") (pinfunction "GND_45") (pintype "unspecified"))
      (node (ref "U2") (pin "46") (pinfunction "GND_46") (pintype "unspecified"))
      (node (ref "U2") (pin "54") (pinfunction "GND_54") (pintype "unspecified"))
      (node (ref "U2") (pin "58") (pinfunction "GND_58") (pintype "unspecified"))
      (node (ref "U2") (pin "59") (pinfunction "GND_59") (pintype "unspecified"))
      (node (ref "U2") (pin "61") (pinfunction "GND_61") (pintype "unspecified"))
      (node (ref "U2") (pin "62") (pinfunction "GND_62") (pintype "unspecified"))
      (node (ref "U2") (pin "63") (pinfunction "GND_63") (pintype "unspecified"))
      (node (ref "U2") (pin "64") (pinfunction "GND_64") (pintype "unspecified"))
      (node (ref "U2") (pin "65") (pinfunction "GND_65") (pintype "unspecified"))
      (node (ref "U2") (pin "69") (pinfunction "GND_69") (pintype "unspecified"))
      (node (ref "U2") (pin "70") (pinfunction "GND_70") (pintype "unspecified"))
      (node (ref "U2") (pin "71") (pinfunction "GND_71") (pintype "unspecified"))
      (node (ref "U2") (pin "72") (pinfunction "GND_72") (pintype "unspecified"))
      (node (ref "U2") (pin "73") (pinfunction "GND_73") (pintype "unspecified"))
      (node (ref "U2") (pin "74") (pinfunction "GND_74") (pintype "unspecified"))
      (node (ref "U2") (pin "75") (pinfunction "GND_75") (pintype "unspecified"))
      (node (ref "U2") (pin "76") (pinfunction "GND_76") (pintype "unspecified"))
      (node (ref "U2") (pin "77") (pinfunction "GND_77") (pintype "unspecified"))
      (node (ref "U2") (pin "78") (pinfunction "GND_78") (pintype "unspecified"))
      (node (ref "U2") (pin "79") (pinfunction "GND_79") (pintype "unspecified"))
      (node (ref "U2") (pin "80") (pinfunction "GND_80") (pintype "unspecified"))
      (node (ref "U2") (pin "81") (pinfunction "GND_81") (pintype "unspecified"))
      (node (ref "U2") (pin "82") (pinfunction "GND_82") (pintype "unspecified"))
      (node (ref "U2") (pin "83") (pinfunction "GND_83") (pintype "unspecified"))
      (node (ref "U2") (pin "84") (pinfunction "GND_84") (pintype "unspecified"))
      (node (ref "U2") (pin "85") (pinfunction "GND_85") (pintype "unspecified"))
      (node (ref "U2") (pin "86") (pinfunction "GND_86") (pintype "unspecified"))
      (node (ref "U2") (pin "87") (pinfunction "GND_87") (pintype "unspecified"))
      (node (ref "U2") (pin "88") (pinfunction "GND_88") (pintype "unspecified"))
      (node (ref "U2") (pin "89") (pinfunction "GND_89") (pintype "unspecified"))
      (node (ref "U2") (pin "91") (pinfunction "GND_91") (pintype "unspecified"))
      (node (ref "U2") (pin "92") (pinfunction "GND_92") (pintype "unspecified"))
      (node (ref "U2") (pin "94") (pinfunction "GND_94") (pintype "unspecified"))
      (node (ref "U3") (pin "1") (pinfunction "C_1") (pintype "unspecified"))
      (node (ref "U5") (pin "1") (pinfunction "VSS_1") (pintype "unspecified"))
      (node (ref "U5") (pin "9") (pinfunction "EP_9") (pintype "unspecified"))
      (node (ref "U6") (pin "2") (pinfunction "GND_2") (pintype "unspecified"))
      (node (ref "U6") (pin "5") (pinfunction "EP_5") (pintype "unspecified"))
      (node (ref "U7") (pin "21") (pinfunction "EP_21") (pintype "unspecified"))
      (node (ref "U7") (pin "9") (pinfunction "GND_9") (pintype "unspecified"))
      (node (ref "U8") (pin "7") (pinfunction "GND_7") (pintype "unspecified"))
      (node (ref "USB2") (pin "1") (pinfunction "SHELL_1") (pintype "unspecified"))
      (node (ref "USB2") (pin "2") (pinfunction "SHELL_2") (pintype "unspecified"))
      (node (ref "USB2") (pin "3") (pinfunction "SHELL_3") (pintype "unspecified"))
      (node (ref "USB2") (pin "4") (pinfunction "SHELL_4") (pintype "unspecified"))
      (node (ref "USB2") (pin "A1B12") (pinfunction "GND_A1B12") (pintype "unspecified"))
      (node (ref "USB2") (pin "B1A12") (pinfunction "GND_B1A12") (pintype "unspecified"))
      (node (ref "USB3") (pin "13") (pinfunction "EH_13") (pintype "unspecified"))
      (node (ref "USB3") (pin "14") (pinfunction "EH_14") (pintype "unspecified"))
      (node (ref "USB3") (pin "A1B12") (pinfunction "GND_A1B12") (pintype "unspecified"))
      (node (ref "USB3") (pin "B1A12") (pinfunction "GND_B1A12") (pintype "unspecified"))
    )
    (net (code "13") (name "GNSS_ANT_PWR") (class "Default")
      (node (ref "R33") (pin "2") (pinfunction "2_2") (pintype "input"))
      (node (ref "U2") (pin "19") (pinfunction "GPIO1_19") (pintype "unspecified"))
      (node (ref "U6") (pin "3") (pinfunction "EN_3") (pintype "unspecified"))
    )
    (net (code "14") (name "GNSS_PWRCTRL") (class "Default")
      (node (ref "R21") (pin "2") (pinfunction "2_2") (pintype "input"))
      (node (ref "U2") (pin "20") (pinfunction "MK_IN_3_20") (pintype "unspecified"))
    )
    (net (code "15") (name "GNSS_RXD") (class "Default")
      (node (ref "R16") (pin "1") (pinfunction "1_1") (pintype "input"))
      (node (ref "U2") (pin "96") (pinfunction "GNSS_RXD_96") (pintype "unspecified"))
      (node (ref "U7") (pin "3") (pinfunction "A4_3") (pintype "unspecified"))
    )
    (net (code "16") (name "GNSS_TXD") (class "Default")
      (node (ref "R15") (pin "1") (pinfunction "1_1") (pintype "input"))
      (node (ref "U2") (pin "95") (pinfunction "GNSS_TXD_95") (pintype "unspecified"))
      (node (ref "U7") (pin "4") (pinfunction "A5_4") (pintype "unspecified"))
    )
    (net (code "17") (name "GPS_PPS") (class "Default")
      (node (ref "LED4") (pin "2") (pinfunction "C_2") (pintype "input"))
      (node (ref "Q1") (pin "3") (pinfunction "C_3") (pintype "input"))
    )
    (net (code "18") (name "GPS_RX") (class "Default")
      (node (ref "R35") (pin "2") (pinfunction "2_2") (pintype "input"))
    )
    (net (code "19") (name "MIC_N") (class "Default")
      (node (ref "L7") (pin "1") (pinfunction "1_1") (pintype "input"))
      (node (ref "R42") (pin "1") (pinfunction "1_1") (pintype "input"))
      (node (ref "U2") (pin "43") (pinfunction "MIC_N_43") (pintype "unspecified"))
    )
    (net (code "20") (name "MIC_P") (class "Default")
      (node (ref "L6") (pin "1") (pinfunction "1_1") (pintype "input"))
      (node (ref "U2") (pin "42") (pinfunction "MIC_P_42") (pintype "unspecified"))
    )
    (net (code "21") (name "MODEM_CTS") (class "Default")
      (node (ref "R34") (pin "2") (pinfunction "2_2") (pintype "input"))
    )
    (net (code "22") (name "MODEM_DTR") (class "Default")
      (node (ref "U7") (pin "16") (pinfunction "B2_16") (pintype "unspecified"))
    )
    (net (code "23") (name "MODEM_DX") (class "Default")
      (node (ref "U7") (pin "11") (pinfunction "B7_11") (pintype "unspecified"))
    )
    (net (code "24") (name "MODEM_PWR") (class "Default")
      (node (ref "R29") (pin "2") (pinfunction "2_2") (pintype "input"))
    )
    (net (code "25") (name "MODEM_RING") (class "Default")
      (node (ref "U7") (pin "18") (pinfunction "B1_18") (pintype "unspecified"))
    )
    (net (code "26") (name "MODEM_RTS") (class "Default")
      (node (ref "R37") (pin "2") (pinfunction "2_2") (pintype "input"))
    )
    (net (code "27") (name "MODEM_TX") (class "Default")
      (node (ref "U7") (pin "10") (pinfunction "B8_10") (pintype "unspecified"))
    )
    (net (code "28") (name "MODEM_USB_N") (class "Default")
      (node (ref "D5") (pin "2") (pinfunction "2_2") (pintype "unspecified"))
      (node (ref "U2") (pin "28") (pinfunction "USB_DM_28") (pintype "unspecified"))
      (node (ref "USB3") (pin "A7") (pinfunction "Dn1_A7") (pintype "unspecified"))
      (node (ref "USB3") (pin "B7") (pinfunction "Dn2_B7") (pintype "unspecified"))
    )
    (net (code "29") (name "MODEM_USB_P") (class "Default")
      (node (ref "D4") (pin "2") (pinfunction "2_2") (pintype "unspecified"))
      (node (ref "U2") (pin "27") (pinfunction "USB_DP_27") (pintype "unspecified"))
      (node (ref "USB3") (pin "A6") (pinfunction "Dp1_A6") (pintype "unspecified"))
      (node (ref "USB3") (pin "B6") (pinfunction "Dp2_B6") (pintype "unspecified"))
    )
    (net (code "30") (name "MODEM_VBUS") (class "Default")
      (node (ref "D6") (pin "1") (pinfunction "C_1") (pintype "unspecified"))
      (node (ref "U2") (pin "24") (pinfunction "VBUS_24") (pintype "unspecified"))
      (node (ref "USB3") (pin "A4B9") (pinfunction "VBUS_A4B9") (pintype "unspecified"))
      (node (ref "USB3") (pin "B4A9") (pinfunction "VBUS_B4A9") (pintype "unspecified"))
    )
    (net (code "31") (name "Net-(C10-Pad2)") (class "Default")
      (node (ref "C10") (pin "2") (pinfunction "2_2") (pintype "input"))
      (node (ref "L3") (pin "1") (pinfunction "1_1") (pintype "input"))
      (node (ref "R22") (pin "1") (pinfunction "1_1") (pintype "input"))
      (node (ref "R23") (pin "1") (pinfunction "1_1") (pintype "input"))
    )
    (net (code "32") (name "Net-(C30-Pad1)") (class "Default")
      (node (ref "C30") (pin "1") (pinfunction "1_1") (pintype "input"))
      (node (ref "R38") (pin "1") (pinfunction "1_1") (pintype "input"))
    )
    (net (code "33") (name "Net-(C31-Pad1)") (class "Default")
      (node (ref "C31") (pin "1") (pinfunction "1_1") (pintype "input"))
      (node (ref "R39") (pin "1") (pinfunction "1_1") (pintype "input"))
    )
    (net (code "34") (name "Net-(C35-Pad1)") (class "Default")
      (node (ref "C35") (pin "1") (pinfunction "1_1") (pintype "input"))
      (node (ref "CN2") (pin "1") (pinfunction "1_1") (pintype "input"))
      (node (ref "L4") (pin "2") (pinfunction "2_2") (pintype "input"))
    )
    (net (code "35") (name "Net-(C36-Pad1)") (class "Default")
      (node (ref "C36") (pin "1") (pinfunction "1_1") (pintype "input"))
      (node (ref "CN2") (pin "2") (pinfunction "2_2") (pintype "input"))
      (node (ref "L5") (pin "2") (pinfunction "2_2") (pintype "input"))
    )
    (net (code "36") (name "Net-(C37-Pad2)") (class "Default")
      (node (ref "C37") (pin "2") (pinfunction "2_2") (pintype "input"))
      (node (ref "C38") (pin "1") (pinfunction "1_1") (pintype "input"))
      (node (ref "C40") (pin "2") (pinfunction "2_2") (pintype "input"))
      (node (ref "C41") (pin "1") (pinfunction "1_1") (pintype "input"))
      (node (ref "CN3") (pin "1") (pinfunction "1_1") (pintype "input"))
      (node (ref "L6") (pin "2") (pinfunction "2_2") (pintype "input"))
    )
    (net (code "37") (name "Net-(C38-Pad2)") (class "Default")
      (node (ref "C38") (pin "2") (pinfunction "2_2") (pintype "input"))
      (node (ref "C39") (pin "1") (pinfunction "1_1") (pintype "input"))
      (node (ref "C41") (pin "2") (pinfunction "2_2") (pintype "input"))
      (node (ref "C42") (pin "1") (pinfunction "1_1") (pintype "input"))
      (node (ref "CN3") (pin "2") (pinfunction "2_2") (pintype "input"))
      (node (ref "L7") (pin "2") (pinfunction "2_2") (pintype "input"))
    )
    (net (code "38") (name "Net-(D1-I{slash}O1-Pad1)") (class "Default")
      (node (ref "D1") (pin "1") (pinfunction "I/O1_1") (pintype "input"))
      (node (ref "R7") (pin "1") (pinfunction "1_1") (pintype "input"))
    )
    (net (code "39") (name "Net-(D1-I{slash}O2-Pad3)") (class "Default")
      (node (ref "D1") (pin "3") (pinfunction "I/O2_3") (pintype "input"))
      (node (ref "R8") (pin "1") (pinfunction "1_1") (pintype "input"))
    )
    (net (code "40") (name "Net-(D2-C)") (class "Default")
      (node (ref "C7") (pin "1") (pinfunction "1_1") (pintype "input"))
      (node (ref "CN1") (pin "2") (pinfunction "2_2") (pintype "input"))
      (node (ref "D2") (pin "1") (pinfunction "C_1") (pintype "unspecified"))
      (node (ref "R20") (pin "1") (pinfunction "1_1") (pintype "input"))
      (node (ref "U2") (pin "116") (pinfunction "GNSS_VBKP_116") (pintype "unspecified"))
    )
    (net (code "41") (name "Net-(LED1-A)") (class "Default")
      (node (ref "LED1") (pin "1") (pinfunction "A_1") (pintype "input"))
      (node (ref "R12") (pin "1") (pinfunction "1_1") (pintype "input"))
    )
    (net (code "42") (name "Net-(LED2-A)") (class "Default")
      (node (ref "LED2") (pin "1") (pinfunction "A_1") (pintype "input"))
      (node (ref "R19") (pin "1") (pinfunction "1_1") (pintype "input"))
    )
    (net (code "43") (name "Net-(LED3-A)") (class "Default")
      (node (ref "LED3") (pin "1") (pinfunction "A_1") (pintype "input"))
      (node (ref "R24") (pin "1") (pinfunction "1_1") (pintype "input"))
    )
    (net (code "44") (name "Net-(LED4-A)") (class "Default")
      (node (ref "LED4") (pin "1") (pinfunction "A_1") (pintype "input"))
      (node (ref "R27") (pin "1") (pinfunction "1_1") (pintype "input"))
    )
    (net (code "45") (name "Net-(Q1-B)") (class "Default")
      (node (ref "Q1") (pin "1") (pinfunction "B_1") (pintype "input"))
      (node (ref "R25") (pin "2") (pinfunction "2_2") (pintype "input"))
      (node (ref "R26") (pin "1") (pinfunction "1_1") (pintype "input"))
    )
    (net (code "46") (name "Net-(Q2-B)") (class "Default")
      (node (ref "Q2") (pin "1") (pinfunction "B_1") (pintype "input"))
      (node (ref "R28") (pin "2") (pinfunction "2_2") (pintype "input"))
      (node (ref "R29") (pin "1") (pinfunction "1_1") (pintype "input"))
    )
    (net (code "47") (name "Net-(RF1-CONT)") (class "Default")
      (node (ref "RF1") (pin "2") (pinfunction "CONT_2") (pintype "unspecified"))
      (node (ref "U2") (pin "60") (pinfunction "RF_ANT_60") (pintype "unspecified"))
    )
    (net (code "48") (name "Net-(RF3-CONT)") (class "Default")
      (node (ref "C9") (pin "1") (pinfunction "1_1") (pintype "input"))
      (node (ref "L3") (pin "2") (pinfunction "2_2") (pintype "input"))
      (node (ref "RF3") (pin "2") (pinfunction "CONT_2") (pintype "unspecified"))
      (node (ref "U4") (pin "2") (pinfunction "A_2") (pintype "unspecified"))
    )
    (net (code "49") (name "Net-(RF4-CONT)") (class "Default")
      (node (ref "RF4") (pin "2") (pinfunction "CONT_2") (pintype "unspecified"))
      (node (ref "U2") (pin "93") (pinfunction "BT_ANT_93") (pintype "unspecified"))
      (node (ref "U3") (pin "2") (pinfunction "A_2") (pintype "unspecified"))
    )
    (net (code "50") (name "Net-(U1-FB)") (class "Default")
      (node (ref "R10") (pin "2") (pinfunction "2_2") (pintype "input"))
      (node (ref "R9") (pin "1") (pinfunction "1_1") (pintype "input"))
      (node (ref "U1") (pin "5") (pinfunction "FB_5") (pintype "unspecified"))
    )
    (net (code "51") (name "Net-(U1-LX)") (class "Default")
      (node (ref "L1") (pin "1") (pinfunction "1_1") (pintype "input"))
      (node (ref "U1") (pin "3") (pinfunction "LX_3") (pintype "unspecified"))
    )
    (net (code "52") (name "Net-(U2-1V8_GNSS)") (class "Default")
      (node (ref "C8") (pin "2") (pinfunction "2_2") (pintype "input"))
      (node (ref "L2") (pin "1") (pinfunction "1_1") (pintype "input"))
      (node (ref "U2") (pin "97") (pinfunction "1V8_GNSS_97") (pintype "unspecified"))
    )
    (net (code "53") (name "Net-(U2-EAR_N)") (class "Default")
      (node (ref "R14") (pin "2") (pinfunction "2_2") (pintype "input"))
      (node (ref "U2") (pin "41") (pinfunction "EAR_N_41") (pintype "unspecified"))
    )
    (net (code "54") (name "Net-(U2-EAR_P)") (class "Default")
      (node (ref "R13") (pin "2") (pinfunction "2_2") (pintype "input"))
      (node (ref "U2") (pin "40") (pinfunction "EAR_P_40") (pintype "unspecified"))
    )
    (net (code "55") (name "Net-(U2-GNSS_ANT)") (class "Default")
      (node (ref "C9") (pin "2") (pinfunction "2_2") (pintype "input"))
      (node (ref "U2") (pin "90") (pinfunction "GNSS_ANT_90") (pintype "unspecified"))
    )
    (net (code "56") (name "Net-(U2-GNSS_PWRCTL)") (class "Default")
      (node (ref "R21") (pin "1") (pinfunction "1_1") (pintype "input"))
      (node (ref "U2") (pin "98") (pinfunction "GNSS_PWRCTL_98") (pintype "unspecified"))
    )
    (net (code "57") (name "Net-(U2-GPIO2)") (class "Default")
      (node (ref "TP7") (pin "1") (pinfunction "1_1") (pintype "unspecified"))
      (node (ref "U2") (pin "26") (pinfunction "GPIO2_26") (pintype "unspecified"))
    )
    (net (code "58") (name "Net-(U2-MK_IN_5)") (class "Default")
      (node (ref "TP10") (pin "1") (pinfunction "1_1") (pintype "unspecified"))
      (node (ref "U2") (pin "68") (pinfunction "MK_IN_5_68") (pintype "unspecified"))
    )
    (net (code "59") (name "Net-(U2-MK_IN_6{slash}I2C3_SCL)") (class "Default")
      (node (ref "TP9") (pin "1") (pinfunction "1_1") (pintype "unspecified"))
      (node (ref "U2") (pin "36") (pinfunction "MK_IN_6/I2C3_SCL_36") (pintype "unspecified"))
    )
    (net (code "60") (name "Net-(U2-MK_OUT_3)") (class "Default")
      (node (ref "TP6") (pin "1") (pinfunction "1_1") (pintype "unspecified"))
      (node (ref "U2") (pin "21") (pinfunction "MK_OUT_3_21") (pintype "unspecified"))
    )
    (net (code "61") (name "Net-(U2-MK_OUT_5)") (class "Default")
      (node (ref "TP11") (pin "1") (pinfunction "1_1") (pintype "unspecified"))
      (node (ref "U2") (pin "67") (pinfunction "MK_OUT_5_67") (pintype "unspecified"))
    )
    (net (code "62") (name "Net-(U2-MK_OUT_6{slash}I2C3_SDA)") (class "Default")
      (node (ref "TP8") (pin "1") (pinfunction "1_1") (pintype "unspecified"))
      (node (ref "U2") (pin "35") (pinfunction "MK_OUT_6/I2C3_SDA_35") (pintype "unspecified"))
    )
    (net (code "63") (name "Net-(U2-NETLIGHT)") (class "Default")
      (node (ref "R19") (pin "2") (pinfunction "2_2") (pintype "input"))
      (node (ref "U2") (pin "52") (pinfunction "NETLIGHT_52") (pintype "unspecified"))
    )
    (net (code "64") (name "Net-(U2-SPI_CLK)") (class "Default")
      (node (ref "TP2") (pin "1") (pinfunction "1_1") (pintype "unspecified"))
      (node (ref "U2") (pin "11") (pinfunction "SPI_CLK_11") (pintype "unspecified"))
    )
    (net (code "65") (name "Net-(U2-SPI_CS)") (class "Default")
      (node (ref "TP3") (pin "1") (pinfunction "1_1") (pintype "unspecified"))
      (node (ref "U2") (pin "12") (pinfunction "SPI_CS_12") (pintype "unspecified"))
    )
    (net (code "66") (name "Net-(U2-SPI_MISO)") (class "Default")
      (node (ref "TP5") (pin "1") (pinfunction "1_1") (pintype "unspecified"))
      (node (ref "U2") (pin "14") (pinfunction "SPI_MISO_14") (pintype "unspecified"))
    )
    (net (code "67") (name "Net-(U2-SPI_MOSI)") (class "Default")
      (node (ref "TP4") (pin "1") (pinfunction "1_1") (pintype "unspecified"))
      (node (ref "U2") (pin "13") (pinfunction "SPI_MOSI_13") (pintype "unspecified"))
    )
    (net (code "68") (name "Net-(U2-STATUS)") (class "Default")
      (node (ref "R24") (pin "2") (pinfunction "2_2") (pintype "input"))
      (node (ref "U2") (pin "66") (pinfunction "STATUS_66") (pintype "unspecified"))
    )
    (net (code "69") (name "Net-(U2-UART3_RXD)") (class "Default")
      (node (ref "R15") (pin "2") (pinfunction "2_2") (pintype "input"))
      (node (ref "U2") (pin "49") (pinfunction "UART3_RXD_49") (pintype "unspecified"))
    )
    (net (code "70") (name "Net-(U2-UART3_TXD)") (class "Default")
      (node (ref "R16") (pin "2") (pinfunction "2_2") (pintype "input"))
      (node (ref "U2") (pin "50") (pinfunction "UART3_TXD_50") (pintype "unspecified"))
    )
    (net (code "71") (name "Net-(U2-USB_BOOT●)") (class "Default")
      (node (ref "SW3") (pin "2") (pinfunction "2_2") (pintype "unspecified"))
      (node (ref "U2") (pin "6") (pinfunction "USB_BOOT●_6") (pintype "unspecified"))
    )
    (net (code "72") (name "Net-(U4-C)") (class "Default")
      (node (ref "RF3") (pin "1") (pinfunction "GND_1") (pintype "unspecified"))
      (node (ref "U4") (pin "1") (pinfunction "C_1") (pintype "unspecified"))
    )
    (net (code "73") (name "Net-(U6-OUT)") (class "Default")
      (node (ref "C25") (pin "1") (pinfunction "1_1") (pintype "input"))
      (node (ref "C26") (pin "1") (pinfunction "1_1") (pintype "input"))
      (node (ref "U6") (pin "1") (pinfunction "OUT_1") (pintype "unspecified"))
    )
    (net (code "74") (name "Net-(U7-B3)") (class "Default")
      (node (ref "R34") (pin "1") (pinfunction "1_1") (pintype "input"))
      (node (ref "U7") (pin "15") (pinfunction "B3_15") (pintype "unspecified"))
    )
    (net (code "75") (name "Net-(U7-B4)") (class "Default")
      (node (ref "R35") (pin "1") (pinfunction "1_1") (pintype "input"))
      (node (ref "U7") (pin "14") (pinfunction "B4_14") (pintype "unspecified"))
    )
    (net (code "76") (name "Net-(U7-B5)") (class "Default")
      (node (ref "R36") (pin "1") (pinfunction "1_1") (pintype "input"))
      (node (ref "U7") (pin "13") (pinfunction "B5_13") (pintype "unspecified"))
    )
    (net (code "77") (name "Net-(U7-B6)") (class "Default")
      (node (ref "R37") (pin "1") (pinfunction "1_1") (pintype "input"))
      (node (ref "U7") (pin "12") (pinfunction "B6_12") (pintype "unspecified"))
    )
    (net (code "78") (name "Net-(U8-Bypass)") (class "Default")
      (node (ref "C32") (pin "1") (pinfunction "1_1") (pintype "input"))
      (node (ref "U8") (pin "2") (pinfunction "Bypass_2") (pintype "unspecified"))
    )
    (net (code "79") (name "Net-(U8-CTRL)") (class "Default")
      (node (ref "R40") (pin "1") (pinfunction "1_1") (pintype "input"))
      (node (ref "R41") (pin "1") (pinfunction "1_1") (pintype "input"))
      (node (ref "U8") (pin "1") (pinfunction "CTRL_1") (pintype "unspecified"))
    )
    (net (code "80") (name "Net-(U8-INN)") (class "Default")
      (node (ref "R39") (pin "2") (pinfunction "2_2") (pintype "input"))
      (node (ref "U8") (pin "4") (pinfunction "INN_4") (pintype "unspecified"))
    )
    (net (code "81") (name "Net-(U8-INP)") (class "Default")
      (node (ref "R38") (pin "2") (pinfunction "2_2") (pintype "input"))
      (node (ref "U8") (pin "3") (pinfunction "INP_3") (pintype "unspecified"))
    )
    (net (code "82") (name "Net-(U8-VON)") (class "Default")
      (node (ref "L4") (pin "1") (pinfunction "1_1") (pintype "input"))
      (node (ref "U8") (pin "5") (pinfunction "VON_5") (pintype "unspecified"))
    )
    (net (code "83") (name "Net-(U8-VoP)") (class "Default")
      (node (ref "L5") (pin "1") (pinfunction "1_1") (pintype "input"))
      (node (ref "U8") (pin "8") (pinfunction "VoP_8") (pintype "unspecified"))
    )
    (net (code "84") (name "Net-(USB2-CC1)") (class "Default")
      (node (ref "R6") (pin "2") (pinfunction "2_2") (pintype "input"))
      (node (ref "USB2") (pin "A5") (pinfunction "CC1_A5") (pintype "unspecified"))
    )
    (net (code "85") (name "Net-(USB2-CC2)") (class "Default")
      (node (ref "R4") (pin "2") (pinfunction "2_2") (pintype "input"))
      (node (ref "USB2") (pin "B5") (pinfunction "CC2_B5") (pintype "unspecified"))
    )
    (net (code "86") (name "Net-(USB2-DN1)") (class "Default")
      (node (ref "D1") (pin "4") (pinfunction "I/O2_4") (pintype "input"))
      (node (ref "USB2") (pin "A7") (pinfunction "DN1_A7") (pintype "unspecified"))
      (node (ref "USB2") (pin "B7") (pinfunction "DN2_B7") (pintype "unspecified"))
    )
    (net (code "87") (name "Net-(USB2-DP1)") (class "Default")
      (node (ref "D1") (pin "6") (pinfunction "I/O1_6") (pintype "input"))
      (node (ref "USB2") (pin "A6") (pinfunction "DP1_A6") (pintype "unspecified"))
      (node (ref "USB2") (pin "B6") (pinfunction "DP2_B6") (pintype "unspecified"))
    )
    (net (code "88") (name "Net-(USB3-CC1)") (class "Default")
      (node (ref "R44") (pin "2") (pinfunction "2_2") (pintype "input"))
      (node (ref "USB3") (pin "A5") (pinfunction "CC1_A5") (pintype "unspecified"))
    )
    (net (code "89") (name "Net-(USB3-CC2)") (class "Default")
      (node (ref "R43") (pin "2") (pinfunction "2_2") (pintype "input"))
      (node (ref "USB3") (pin "B5") (pinfunction "CC2_B5") (pintype "unspecified"))
    )
    (net (code "90") (name "PPS") (class "Default")
      (node (ref "R26") (pin "2") (pinfunction "2_2") (pintype "input"))
      (node (ref "U2") (pin "100") (pinfunction "1PPS_100") (pintype "unspecified"))
    )
    (net (code "91") (name "PWRKEY") (class "Default")
      (node (ref "Q2") (pin "3") (pinfunction "C_3") (pintype "input"))
      (node (ref "TP1") (pin "1") (pinfunction "1_1") (pintype "unspecified"))
      (node (ref "U2") (pin "1") (pinfunction "PWRKEY_1") (pintype "unspecified"))
    )
    (net (code "92") (name "RI") (class "Default")
      (node (ref "U2") (pin "4") (pinfunction "RI_4") (pintype "unspecified"))
      (node (ref "U7") (pin "19") (pinfunction "A1_19") (pintype "unspecified"))
    )
    (net (code "93") (name "RST") (class "Default")
      (node (ref "C1") (pin "1") (pinfunction "1_1") (pintype "input"))
      (node (ref "ESP1") (pin "45") (pinfunction "EN_45") (pintype "unspecified"))
      (node (ref "R1") (pin "1") (pinfunction "1_1") (pintype "input"))
      (node (ref "SW1") (pin "2") (pinfunction "2_2") (pintype "unspecified"))
    )
    (net (code "94") (name "RTS") (class "Default")
      (node (ref "U2") (pin "8") (pinfunction "RTS_8") (pintype "unspecified"))
      (node (ref "U7") (pin "5") (pinfunction "A6_5") (pintype "unspecified"))
    )
    (net (code "95") (name "RXD") (class "Default")
      (node (ref "U2") (pin "10") (pinfunction "RXD_10") (pintype "unspecified"))
      (node (ref "U7") (pin "6") (pinfunction "A7_6") (pintype "unspecified"))
    )
    (net (code "96") (name "SIM_CLK") (class "Default")
      (node (ref "CARD1") (pin "C3") (pinfunction "CLK_C3") (pintype "unspecified"))
      (node (ref "D3") (pin "3") (pinfunction "3_3") (pintype "unspecified"))
      (node (ref "R30") (pin "2") (pinfunction "2_2") (pintype "input"))
      (node (ref "U5") (pin "6") (pinfunction "CLK_6") (pintype "unspecified"))
    )
    (net (code "97") (name "SIM_DATA") (class "Default")
      (node (ref "CARD1") (pin "C7") (pinfunction "I/O_C7") (pintype "unspecified"))
      (node (ref "D3") (pin "1") (pinfunction "1_1") (pintype "unspecified"))
      (node (ref "R32") (pin "2") (pinfunction "2_2") (pintype "input"))
      (node (ref "U5") (pin "3") (pinfunction "I/O_3") (pintype "unspecified"))
    )
    (net (code "98") (name "SIM_RST") (class "Default")
      (node (ref "CARD1") (pin "C2") (pinfunction "RST_C2") (pintype "unspecified"))
      (node (ref "D3") (pin "4") (pinfunction "4_4") (pintype "unspecified"))
      (node (ref "R31") (pin "2") (pinfunction "2_2") (pintype "input"))
      (node (ref "U5") (pin "7") (pinfunction "RST_7") (pintype "unspecified"))
    )
    (net (code "99") (name "SPK_N") (class "Default")
      (node (ref "C31") (pin "2") (pinfunction "2_2") (pintype "input"))
      (node (ref "R14") (pin "1") (pinfunction "1_1") (pintype "input"))
    )
    (net (code "100") (name "SPK_P") (class "Default")
      (node (ref "C30") (pin "2") (pinfunction "2_2") (pintype "input"))
      (node (ref "R13") (pin "1") (pinfunction "1_1") (pintype "input"))
    )
    (net (code "101") (name "SPK_SD") (class "Default")
      (node (ref "R40") (pin "2") (pinfunction "2_2") (pintype "input"))
      (node (ref "U2") (pin "48") (pinfunction "GPIO3_48") (pintype "unspecified"))
    )
    (net (code "102") (name "TP2") (class "Default")
      (node (ref "C6") (pin "1") (pinfunction "1_1") (pintype "input"))
      (node (ref "R17") (pin "1") (pinfunction "1_1") (pintype "input"))
      (node (ref "R18") (pin "2") (pinfunction "2_2") (pintype "input"))
      (node (ref "U2") (pin "51") (pinfunction "VBAT_ADC_51") (pintype "unspecified"))
    )
    (net (code "103") (name "TP18") (class "Default")
      (node (ref "U2") (pin "53") (pinfunction "GPIO4_53") (pintype "unspecified"))
    )
    (net (code "104") (name "TXD") (class "Default")
      (node (ref "U2") (pin "9") (pinfunction "TXD_9") (pintype "unspecified"))
      (node (ref "U7") (pin "7") (pinfunction "A8_7") (pintype "unspecified"))
    )
    (net (code "105") (name "USB_N") (class "Default")
      (node (ref "ESP1") (pin "23") (pinfunction "IO19_23") (pintype "unspecified"))
      (node (ref "R8") (pin "2") (pinfunction "2_2") (pintype "input"))
    )
    (net (code "106") (name "USB_P") (class "Default")
      (node (ref "ESP1") (pin "24") (pinfunction "IO20_24") (pintype "unspecified"))
      (node (ref "R7") (pin "2") (pinfunction "2_2") (pintype "input"))
    )
    (net (code "107") (name "USIM_CLK") (class "Default")
      (node (ref "C13") (pin "1") (pinfunction "1_1") (pintype "input"))
      (node (ref "R30") (pin "1") (pinfunction "1_1") (pintype "input"))
      (node (ref "U2") (pin "32") (pinfunction "USIM1_CLK_32") (pintype "unspecified"))
    )
    (net (code "108") (name "USIM_DATA") (class "Default")
      (node (ref "C15") (pin "1") (pinfunction "1_1") (pintype "input"))
      (node (ref "R32") (pin "1") (pinfunction "1_1") (pintype "input"))
      (node (ref "U2") (pin "31") (pinfunction "USIM1_DATA_31") (pintype "unspecified"))
    )
    (net (code "109") (name "USIM_RST") (class "Default")
      (node (ref "C14") (pin "1") (pinfunction "1_1") (pintype "input"))
      (node (ref "R31") (pin "1") (pinfunction "1_1") (pintype "input"))
      (node (ref "U2") (pin "33") (pinfunction "USIM1_RST_33") (pintype "unspecified"))
    )
    (net (code "110") (name "USIM_VDD") (class "Default")
      (node (ref "C11") (pin "1") (pinfunction "1_1") (pintype "input"))
      (node (ref "C12") (pin "1") (pinfunction "1_1") (pintype "input"))
      (node (ref "C16") (pin "1") (pinfunction "1_1") (pintype "input"))
      (node (ref "CARD1") (pin "C1") (pinfunction "VCC_C1") (pintype "unspecified"))
      (node (ref "D3") (pin "5") (pinfunction "5_5") (pintype "unspecified"))
      (node (ref "U2") (pin "30") (pinfunction "USIM1_VDD_30") (pintype "unspecified"))
      (node (ref "U5") (pin "8") (pinfunction "VDD_8") (pintype "unspecified"))
    )
    (net (code "111") (name "VBAT") (class "Default")
      (node (ref "R17") (pin "2") (pinfunction "2_2") (pintype "input"))
    )
    (net (code "112") (name "VDD_AUX") (class "Default")
      (node (ref "C22") (pin "1") (pinfunction "1_1") (pintype "input"))
      (node (ref "R22") (pin "2") (pinfunction "2_2") (pintype "input"))
      (node (ref "U2") (pin "99") (pinfunction "VDD_2V8_99") (pintype "unspecified"))
    )
    (net (code "113") (name "VDD_GPS") (class "Default")
      (node (ref "R20") (pin "2") (pinfunction "2_2") (pintype "input"))
      (node (ref "R23") (pin "2") (pinfunction "2_2") (pintype "input"))
    )
    (net (code "114") (name "unconnected-(C35-Pad2)") (class "Default")
      (node (ref "C35") (pin "2") (pinfunction "2_2") (pintype "input"))
    )
    (net (code "115") (name "unconnected-(C36-Pad2)") (class "Default")
      (node (ref "C36") (pin "2") (pinfunction "2_2") (pintype "input"))
    )
    (net (code "116") (name "unconnected-(CARD1-Pad1)") (class "Default")
      (node (ref "CARD1") (pin "1") (pinfunction "1_1") (pintype "unspecified"))
    )
    (net (code "117") (name "unconnected-(CARD1-Pad2)") (class "Default")
      (node (ref "CARD1") (pin "2") (pinfunction "2_2") (pintype "unspecified"))
    )
    (net (code "118") (name "unconnected-(CARD1-VPP-PadC6)") (class "Default")
      (node (ref "CARD1") (pin "C6") (pinfunction "VPP_C6") (pintype "unspecified+no_connect"))
    )
    (net (code "119") (name "unconnected-(ESP1-3V3-Pad3)") (class "Default")
      (node (ref "ESP1") (pin "3") (pinfunction "3V3_3") (pintype "unspecified"))
    )
    (net (code "120") (name "unconnected-(ESP1-GND-Pad1)") (class "Default")
      (node (ref "ESP1") (pin "1") (pinfunction "GND_1") (pintype "unspecified"))
    )
    (net (code "121") (name "unconnected-(ESP1-GND-Pad2)") (class "Default")
      (node (ref "ESP1") (pin "2") (pinfunction "GND_2") (pintype "unspecified"))
    )
    (net (code "122") (name "unconnected-(ESP1-GND-Pad42)") (class "Default")
      (node (ref "ESP1") (pin "42") (pinfunction "GND_42") (pintype "unspecified"))
    )
    (net (code "123") (name "unconnected-(ESP1-GND-Pad43)") (class "Default")
      (node (ref "ESP1") (pin "43") (pinfunction "GND_43") (pintype "unspecified"))
    )
    (net (code "124") (name "unconnected-(ESP1-GND-Pad46)") (class "Default")
      (node (ref "ESP1") (pin "46") (pinfunction "GND_46") (pintype "unspecified"))
    )
    (net (code "125") (name "unconnected-(ESP1-GND-Pad47)") (class "Default")
      (node (ref "ESP1") (pin "47") (pinfunction "GND_47") (pintype "unspecified"))
    )
    (net (code "126") (name "unconnected-(ESP1-GND-Pad48)") (class "Default")
      (node (ref "ESP1") (pin "48") (pinfunction "GND_48") (pintype "unspecified"))
    )
    (net (code "127") (name "unconnected-(ESP1-GND-Pad49)") (class "Default")
      (node (ref "ESP1") (pin "49") (pinfunction "GND_49") (pintype "unspecified"))
    )
    (net (code "128") (name "unconnected-(ESP1-GND-Pad50)") (class "Default")
      (node (ref "ESP1") (pin "50") (pinfunction "GND_50") (pintype "unspecified"))
    )
    (net (code "129") (name "unconnected-(ESP1-GND-Pad51)") (class "Default")
      (node (ref "ESP1") (pin "51") (pinfunction "GND_51") (pintype "unspecified"))
    )
    (net (code "130") (name "unconnected-(ESP1-GND-Pad52)") (class "Default")
      (node (ref "ESP1") (pin "52") (pinfunction "GND_52") (pintype "unspecified"))
    )
    (net (code "131") (name "unconnected-(ESP1-GND-Pad53)") (class "Default")
      (node (ref "ESP1") (pin "53") (pinfunction "GND_53") (pintype "unspecified"))
    )
    (net (code "132") (name "unconnected-(ESP1-GND-Pad54)") (class "Default")
      (node (ref "ESP1") (pin "54") (pinfunction "GND_54") (pintype "unspecified"))
    )
    (net (code "133") (name "unconnected-(ESP1-GND-Pad55)") (class "Default")
      (node (ref "ESP1") (pin "55") (pinfunction "GND_55") (pintype "unspecified"))
    )
    (net (code "134") (name "unconnected-(ESP1-GND-Pad56)") (class "Default")
      (node (ref "ESP1") (pin "56") (pinfunction "GND_56") (pintype "unspecified"))
    )
    (net (code "135") (name "unconnected-(ESP1-GND-Pad57)") (class "Default")
      (node (ref "ESP1") (pin "57") (pinfunction "GND_57") (pintype "unspecified"))
    )
    (net (code "136") (name "unconnected-(ESP1-GND-Pad58)") (class "Default")
      (node (ref "ESP1") (pin "58") (pinfunction "GND_58") (pintype "unspecified"))
    )
    (net (code "137") (name "unconnected-(ESP1-GND-Pad59)") (class "Default")
      (node (ref "ESP1") (pin "59") (pinfunction "GND_59") (pintype "unspecified"))
    )
    (net (code "138") (name "unconnected-(ESP1-GND-Pad60)") (class "Default")
      (node (ref "ESP1") (pin "60") (pinfunction "GND_60") (pintype "unspecified"))
    )
    (net (code "139") (name "unconnected-(ESP1-GND-Pad61)") (class "Default")
      (node (ref "ESP1") (pin "61") (pinfunction "GND_61") (pintype "unspecified"))
    )
    (net (code "140") (name "unconnected-(ESP1-GND-Pad62)") (class "Default")
      (node (ref "ESP1") (pin "62") (pinfunction "GND_62") (pintype "unspecified"))
    )
    (net (code "141") (name "unconnected-(ESP1-GND-Pad63)") (class "Default")
      (node (ref "ESP1") (pin "63") (pinfunction "GND_63") (pintype "unspecified"))
    )
    (net (code "142") (name "unconnected-(ESP1-GND-Pad64)") (class "Default")
      (node (ref "ESP1") (pin "64") (pinfunction "GND_64") (pintype "unspecified"))
    )
    (net (code "143") (name "unconnected-(ESP1-GND-Pad65)") (class "Default")
      (node (ref "ESP1") (pin "65") (pinfunction "GND_65") (pintype "unspecified"))
    )
    (net (code "144") (name "unconnected-(ESP1-IO1-Pad5)") (class "Default")
      (node (ref "ESP1") (pin "5") (pinfunction "IO1_5") (pintype "unspecified"))
    )
    (net (code "145") (name "unconnected-(ESP1-IO2-Pad6)") (class "Default")
      (node (ref "ESP1") (pin "6") (pinfunction "IO2_6") (pintype "unspecified"))
    )
    (net (code "146") (name "unconnected-(ESP1-IO3-Pad7)") (class "Default")
      (node (ref "ESP1") (pin "7") (pinfunction "IO3_7") (pintype "unspecified"))
    )
    (net (code "147") (name "unconnected-(ESP1-IO4-Pad8)") (class "Default")
      (node (ref "ESP1") (pin "8") (pinfunction "IO4_8") (pintype "unspecified"))
    )
    (net (code "148") (name "unconnected-(ESP1-IO5-Pad9)") (class "Default")
      (node (ref "ESP1") (pin "9") (pinfunction "IO5_9") (pintype "unspecified"))
    )
    (net (code "149") (name "unconnected-(ESP1-IO6-Pad10)") (class "Default")
      (node (ref "ESP1") (pin "10") (pinfunction "IO6_10") (pintype "unspecified"))
    )
    (net (code "150") (name "unconnected-(ESP1-IO7-Pad11)") (class "Default")
      (node (ref "ESP1") (pin "11") (pinfunction "IO7_11") (pintype "unspecified"))
    )
    (net (code "151") (name "unconnected-(ESP1-IO8-Pad12)") (class "Default")
      (node (ref "ESP1") (pin "12") (pinfunction "IO8_12") (pintype "unspecified"))
    )
    (net (code "152") (name "unconnected-(ESP1-IO9-Pad13)") (class "Default")
      (node (ref "ESP1") (pin "13") (pinfunction "IO9_13") (pintype "unspecified"))
    )
    (net (code "153") (name "unconnected-(ESP1-IO10-Pad14)") (class "Default")
      (node (ref "ESP1") (pin "14") (pinfunction "IO10_14") (pintype "unspecified"))
    )
    (net (code "154") (name "unconnected-(ESP1-IO11-Pad15)") (class "Default")
      (node (ref "ESP1") (pin "15") (pinfunction "IO11_15") (pintype "unspecified"))
    )
    (net (code "155") (name "unconnected-(ESP1-IO12-Pad16)") (class "Default")
      (node (ref "ESP1") (pin "16") (pinfunction "IO12_16") (pintype "unspecified"))
    )
    (net (code "156") (name "unconnected-(ESP1-IO13-Pad17)") (class "Default")
      (node (ref "ESP1") (pin "17") (pinfunction "IO13_17") (pintype "unspecified"))
    )
    (net (code "157") (name "unconnected-(ESP1-IO14-Pad18)") (class "Default")
      (node (ref "ESP1") (pin "18") (pinfunction "IO14_18") (pintype "unspecified"))
    )
    (net (code "158") (name "unconnected-(ESP1-IO15-Pad19)") (class "Default")
      (node (ref "ESP1") (pin "19") (pinfunction "IO15_19") (pintype "unspecified"))
    )
    (net (code "159") (name "unconnected-(ESP1-IO16-Pad20)") (class "Default")
      (node (ref "ESP1") (pin "20") (pinfunction "IO16_20") (pintype "unspecified"))
    )
    (net (code "160") (name "unconnected-(ESP1-IO17-Pad21)") (class "Default")
      (node (ref "ESP1") (pin "21") (pinfunction "IO17_21") (pintype "unspecified"))
    )
    (net (code "161") (name "unconnected-(ESP1-IO18-Pad22)") (class "Default")
      (node (ref "ESP1") (pin "22") (pinfunction "IO18_22") (pintype "unspecified"))
    )
    (net (code "162") (name "unconnected-(ESP1-IO21-Pad25)") (class "Default")
      (node (ref "ESP1") (pin "25") (pinfunction "IO21_25") (pintype "unspecified"))
    )
    (net (code "163") (name "unconnected-(ESP1-IO26-Pad26)") (class "Default")
      (node (ref "ESP1") (pin "26") (pinfunction "IO26_26") (pintype "unspecified"))
    )
    (net (code "164") (name "unconnected-(ESP1-IO33-Pad28)") (class "Default")
      (node (ref "ESP1") (pin "28") (pinfunction "IO33_28") (pintype "unspecified"))
    )
    (net (code "165") (name "unconnected-(ESP1-IO34-Pad29)") (class "Default")
      (node (ref "ESP1") (pin "29") (pinfunction "IO34_29") (pintype "unspecified"))
    )
    (net (code "166") (name "unconnected-(ESP1-IO35-Pad31)") (class "Default")
      (node (ref "ESP1") (pin "31") (pinfunction "IO35_31") (pintype "unspecified"))
    )
    (net (code "167") (name "unconnected-(ESP1-IO36-Pad32)") (class "Default")
      (node (ref "ESP1") (pin "32") (pinfunction "IO36_32") (pintype "unspecified"))
    )
    (net (code "168") (name "unconnected-(ESP1-IO37-Pad33)") (class "Default")
      (node (ref "ESP1") (pin "33") (pinfunction "IO37_33") (pintype "unspecified"))
    )
    (net (code "169") (name "unconnected-(ESP1-IO38-Pad34)") (class "Default")
      (node (ref "ESP1") (pin "34") (pinfunction "IO38_34") (pintype "unspecified"))
    )
    (net (code "170") (name "unconnected-(ESP1-IO39-Pad35)") (class "Default")
      (node (ref "ESP1") (pin "35") (pinfunction "IO39_35") (pintype "unspecified"))
    )
    (net (code "171") (name "unconnected-(ESP1-IO40-Pad36)") (class "Default")
      (node (ref "ESP1") (pin "36") (pinfunction "IO40_36") (pintype "unspecified"))
    )
    (net (code "172") (name "unconnected-(ESP1-IO41-Pad37)") (class "Default")
      (node (ref "ESP1") (pin "37") (pinfunction "IO41_37") (pintype "unspecified"))
    )
    (net (code "173") (name "unconnected-(ESP1-IO42-Pad38)") (class "Default")
      (node (ref "ESP1") (pin "38") (pinfunction "IO42_38") (pintype "unspecified"))
    )
    (net (code "174") (name "unconnected-(ESP1-IO45-Pad41)") (class "Default")
      (node (ref "ESP1") (pin "41") (pinfunction "IO45_41") (pintype "unspecified"))
    )
    (net (code "175") (name "unconnected-(ESP1-IO46-Pad44)") (class "Default")
      (node (ref "ESP1") (pin "44") (pinfunction "IO46_44") (pintype "unspecified"))
    )
    (net (code "176") (name "unconnected-(ESP1-IO47-Pad27)") (class "Default")
      (node (ref "ESP1") (pin "27") (pinfunction "IO47_27") (pintype "unspecified"))
    )
    (net (code "177") (name "unconnected-(ESP1-IO48-Pad30)") (class "Default")
      (node (ref "ESP1") (pin "30") (pinfunction "IO48_30") (pintype "unspecified"))
    )
    (net (code "178") (name "unconnected-(ESP1-RXD0-Pad40)") (class "Default")
      (node (ref "ESP1") (pin "40") (pinfunction "RXD0_40") (pintype "unspecified"))
    )
    (net (code "179") (name "unconnected-(ESP1-TXD0-Pad39)") (class "Default")
      (node (ref "ESP1") (pin "39") (pinfunction "TXD0_39") (pintype "unspecified"))
    )
    (net (code "180") (name "unconnected-(Q3-D1-Pad6)") (class "Default")
      (node (ref "Q3") (pin "6") (pinfunction "D1_6") (pintype "unspecified"))
    )
    (net (code "181") (name "unconnected-(Q3-D1-Pad7)") (class "Default")
      (node (ref "Q3") (pin "7") (pinfunction "D1_7") (pintype "unspecified"))
    )
    (net (code "182") (name "unconnected-(Q3-D2-Pad3)") (class "Default")
      (node (ref "Q3") (pin "3") (pinfunction "D2_3") (pintype "unspecified"))
    )
    (net (code "183") (name "unconnected-(Q3-D2-Pad8)") (class "Default")
      (node (ref "Q3") (pin "8") (pinfunction "D2_8") (pintype "unspecified"))
    )
    (net (code "184") (name "unconnected-(Q3-G1-Pad2)") (class "Default")
      (node (ref "Q3") (pin "2") (pinfunction "G1_2") (pintype "unspecified"))
    )
    (net (code "185") (name "unconnected-(Q3-G2-Pad5)") (class "Default")
      (node (ref "Q3") (pin "5") (pinfunction "G2_5") (pintype "unspecified"))
    )
    (net (code "186") (name "unconnected-(Q3-S1-Pad1)") (class "Default")
      (node (ref "Q3") (pin "1") (pinfunction "S1_1") (pintype "unspecified"))
    )
    (net (code "187") (name "unconnected-(Q3-S2-Pad4)") (class "Default")
      (node (ref "Q3") (pin "4") (pinfunction "S2_4") (pintype "unspecified"))
    )
    (net (code "188") (name "unconnected-(RF4-GND-Pad3)") (class "Default")
      (node (ref "RF4") (pin "3") (pinfunction "GND_3") (pintype "unspecified"))
    )
    (net (code "189") (name "unconnected-(SW4-Pad1)") (class "Default")
      (node (ref "SW4") (pin "1") (pinfunction "1_1") (pintype "input"))
    )
    (net (code "190") (name "unconnected-(SW4-Pad2)") (class "Default")
      (node (ref "SW4") (pin "2") (pinfunction "2_2") (pintype "input"))
    )
    (net (code "191") (name "unconnected-(SW4-Pad3)") (class "Default")
      (node (ref "SW4") (pin "3") (pinfunction "3_3") (pintype "input"))
    )
    (net (code "192") (name "unconnected-(U2-ADC-Pad25)") (class "Default")
      (node (ref "U2") (pin "25") (pinfunction "ADC_25") (pintype "unspecified+no_connect"))
    )
    (net (code "193") (name "unconnected-(U2-CAM_I2C_SCL-Pad118)") (class "Default")
      (node (ref "U2") (pin "118") (pinfunction "CAM_I2C_SCL_118") (pintype "unspecified+no_connect"))
    )
    (net (code "194") (name "unconnected-(U2-CAM_I2C_SDA-Pad117)") (class "Default")
      (node (ref "U2") (pin "117") (pinfunction "CAM_I2C_SDA_117") (pintype "unspecified+no_connect"))
    )
    (net (code "195") (name "unconnected-(U2-CAM_MCLK-Pad121)") (class "Default")
      (node (ref "U2") (pin "121") (pinfunction "CAM_MCLK_121") (pintype "unspecified+no_connect"))
    )
    (net (code "196") (name "unconnected-(U2-CAM_PWDN-Pad119)") (class "Default")
      (node (ref "U2") (pin "119") (pinfunction "CAM_PWDN_119") (pintype "unspecified+no_connect"))
    )
    (net (code "197") (name "unconnected-(U2-CAM_RST-Pad120)") (class "Default")
      (node (ref "U2") (pin "120") (pinfunction "CAM_RST_120") (pintype "unspecified+no_connect"))
    )
    (net (code "198") (name "unconnected-(U2-CAM_SPI_CLK-Pad124)") (class "Default")
      (node (ref "U2") (pin "124") (pinfunction "CAM_SPI_CLK_124") (pintype "unspecified+no_connect"))
    )
    (net (code "199") (name "unconnected-(U2-CAM_SPI_D0-Pad122)") (class "Default")
      (node (ref "U2") (pin "122") (pinfunction "CAM_SPI_D0_122") (pintype "unspecified+no_connect"))
    )
    (net (code "200") (name "unconnected-(U2-CAM_SPI_D1-Pad123)") (class "Default")
      (node (ref "U2") (pin "123") (pinfunction "CAM_SPI_D1_123") (pintype "unspecified+no_connect"))
    )
    (net (code "201") (name "unconnected-(U2-DCD-Pad5)") (class "Default")
      (node (ref "U2") (pin "5") (pinfunction "DCD_5") (pintype "unspecified+no_connect"))
    )
    (net (code "202") (name "unconnected-(U2-I2C_SCL-Pad38)") (class "Default")
      (node (ref "U2") (pin "38") (pinfunction "I2C_SCL_38") (pintype "unspecified+no_connect"))
    )
    (net (code "203") (name "unconnected-(U2-I2C_SDA-Pad37)") (class "Default")
      (node (ref "U2") (pin "37") (pinfunction "I2C_SDA_37") (pintype "unspecified+no_connect"))
    )
    (net (code "204") (name "unconnected-(U2-LCD_BL_PWM-Pad101)") (class "Default")
      (node (ref "U2") (pin "101") (pinfunction "LCD_BL_PWM_101") (pintype "unspecified+no_connect"))
    )
    (net (code "205") (name "unconnected-(U2-LCD_DCX-Pad107)") (class "Default")
      (node (ref "U2") (pin "107") (pinfunction "LCD_DCX_107") (pintype "unspecified+no_connect"))
    )
    (net (code "206") (name "unconnected-(U2-LCD_RST-Pad106)") (class "Default")
      (node (ref "U2") (pin "106") (pinfunction "LCD_RST_106") (pintype "unspecified+no_connect"))
    )
    (net (code "207") (name "unconnected-(U2-LCD_SPI_CLK-Pad102)") (class "Default")
      (node (ref "U2") (pin "102") (pinfunction "LCD_SPI_CLK_102") (pintype "unspecified+no_connect"))
    )
    (net (code "208") (name "unconnected-(U2-LCD_SPI_CS-Pad105)") (class "Default")
      (node (ref "U2") (pin "105") (pinfunction "LCD_SPI_CS_105") (pintype "unspecified+no_connect"))
    )
    (net (code "209") (name "unconnected-(U2-LCD_SPI_RXD-Pad104)") (class "Default")
      (node (ref "U2") (pin "104") (pinfunction "LCD_SPI_RXD_104") (pintype "unspecified+no_connect"))
    )
    (net (code "210") (name "unconnected-(U2-LCD_SPI_TXD-Pad103)") (class "Default")
      (node (ref "U2") (pin "103") (pinfunction "LCD_SPI_TXD_103") (pintype "unspecified+no_connect"))
    )
    (net (code "211") (name "unconnected-(U2-MK_IN_2-Pad47)") (class "Default")
      (node (ref "U2") (pin "47") (pinfunction "MK_IN_2_47") (pintype "unspecified+no_connect"))
    )
    (net (code "212") (name "unconnected-(U2-MK_OUT_2-Pad44)") (class "Default")
      (node (ref "U2") (pin "44") (pinfunction "MK_OUT_2_44") (pintype "unspecified+no_connect"))
    )
    (net (code "213") (name "unconnected-(U2-NC-Pad113)") (class "Default")
      (node (ref "U2") (pin "113") (pinfunction "NC_113") (pintype "unspecified+no_connect"))
    )
    (net (code "214") (name "unconnected-(U2-NC-Pad114)") (class "Default")
      (node (ref "U2") (pin "114") (pinfunction "NC_114") (pintype "unspecified+no_connect"))
    )
    (net (code "215") (name "unconnected-(U2-NC-Pad115)") (class "Default")
      (node (ref "U2") (pin "115") (pinfunction "NC_115") (pintype "unspecified+no_connect"))
    )
    (net (code "216") (name "unconnected-(U2-RESET-Pad16)") (class "Default")
      (node (ref "U2") (pin "16") (pinfunction "RESET_16") (pintype "unspecified+no_connect"))
    )
    (net (code "217") (name "unconnected-(U2-UART_LOG_RX-Pad22)") (class "Default")
      (node (ref "U2") (pin "22") (pinfunction "UART_LOG_RX_22") (pintype "unspecified+no_connect"))
    )
    (net (code "218") (name "unconnected-(U2-UART_LOG_TX-Pad23)") (class "Default")
      (node (ref "U2") (pin "23") (pinfunction "UART_LOG_TX_23") (pintype "unspecified+no_connect"))
    )
    (net (code "219") (name "unconnected-(U2-USIM1_DET-Pad34)") (class "Default")
      (node (ref "U2") (pin "34") (pinfunction "USIM1_DET_34") (pintype "unspecified+no_connect"))
    )
    (net (code "220") (name "unconnected-(U2-USIM2_CLK-Pad109)") (class "Default")
      (node (ref "U2") (pin "109") (pinfunction "USIM2_CLK_109") (pintype "unspecified+no_connect"))
    )
    (net (code "221") (name "unconnected-(U2-USIM2_DATA-Pad108)") (class "Default")
      (node (ref "U2") (pin "108") (pinfunction "USIM2_DATA_108") (pintype "unspecified+no_connect"))
    )
    (net (code "222") (name "unconnected-(U2-USIM2_DET-Pad112)") (class "Default")
      (node (ref "U2") (pin "112") (pinfunction "USIM2_DET_112") (pintype "unspecified+no_connect"))
    )
    (net (code "223") (name "unconnected-(U2-USIM2_RST-Pad111)") (class "Default")
      (node (ref "U2") (pin "111") (pinfunction "USIM2_RST_111") (pintype "unspecified+no_connect"))
    )
    (net (code "224") (name "unconnected-(U2-USIM2_VDD-Pad110)") (class "Default")
      (node (ref "U2") (pin "110") (pinfunction "USIM2_VDD_110") (pintype "unspecified+no_connect"))
    )
    (net (code "225") (name "unconnected-(U5-NULL-Pad2)") (class "Default")
      (node (ref "U5") (pin "2") (pinfunction "NULL_2") (pintype "unspecified"))
    )
    (net (code "226") (name "unconnected-(U5-NULL-Pad4)") (class "Default")
      (node (ref "U5") (pin "4") (pinfunction "NULL_4") (pintype "unspecified+no_connect"))
    )
    (net (code "227") (name "unconnected-(U5-NULL-Pad5)") (class "Default")
      (node (ref "U5") (pin "5") (pinfunction "NULL_5") (pintype "unspecified+no_connect"))
    )
    (net (code "228") (name "unconnected-(U9-BAT-Pad5)") (class "Default")
      (node (ref "U9") (pin "5") (pinfunction "BAT_5") (pintype "unspecified"))
    )
    (net (code "229") (name "unconnected-(U9-CHRG#-Pad7)") (class "Default")
      (node (ref "U9") (pin "7") (pinfunction "CHRG#_7") (pintype "unspecified"))
    )
    (net (code "230") (name "unconnected-(U9-DONE#-Pad6)") (class "Default")
      (node (ref "U9") (pin "6") (pinfunction "DONE#_6") (pintype "unspecified"))
    )
    (net (code "231") (name "unconnected-(U9-FB-Pad8)") (class "Default")
      (node (ref "U9") (pin "8") (pinfunction "FB_8") (pintype "unspecified"))
    )
    (net (code "232") (name "unconnected-(U9-GND-Pad3)") (class "Default")
      (node (ref "U9") (pin "3") (pinfunction "GND_3") (pintype "unspecified"))
    )
    (net (code "233") (name "unconnected-(U9-ISET-Pad2)") (class "Default")
      (node (ref "U9") (pin "2") (pinfunction "ISET_2") (pintype "unspecified"))
    )
    (net (code "234") (name "unconnected-(U9-PAD-Pad9)") (class "Default")
      (node (ref "U9") (pin "9") (pinfunction "PAD_9") (pintype "unspecified"))
    )
    (net (code "235") (name "unconnected-(U9-TEMP-Pad1)") (class "Default")
      (node (ref "U9") (pin "1") (pinfunction "TEMP_1") (pintype "unspecified"))
    )
    (net (code "236") (name "unconnected-(U9-VIN-Pad4)") (class "Default")
      (node (ref "U9") (pin "4") (pinfunction "VIN_4") (pintype "unspecified"))
    )
    (net (code "237") (name "unconnected-(U10-BATN-Pad4)") (class "Default")
      (node (ref "U10") (pin "4") (pinfunction "BATN_4") (pintype "unspecified"))
    )
    (net (code "238") (name "unconnected-(U10-BATN-Pad5)") (class "Default")
      (node (ref "U10") (pin "5") (pinfunction "BATN_5") (pintype "unspecified"))
    )
    (net (code "239") (name "unconnected-(U10-BYPS-Pad6)") (class "Default")
      (node (ref "U10") (pin "6") (pinfunction "BYPS_6") (pintype "unspecified"))
    )
    (net (code "240") (name "unconnected-(U10-NC-Pad7)") (class "Default")
      (node (ref "U10") (pin "7") (pinfunction "NC_7") (pintype "unspecified"))
    )
    (net (code "241") (name "unconnected-(U10-PCKN-Pad2)") (class "Default")
      (node (ref "U10") (pin "2") (pinfunction "PCKN_2") (pintype "unspecified"))
    )
    (net (code "242") (name "unconnected-(U10-PCKN-Pad3)") (class "Default")
      (node (ref "U10") (pin "3") (pinfunction "PCKN_3") (pintype "unspecified"))
    )
    (net (code "243") (name "unconnected-(U10-PCKP-Pad1)") (class "Default")
      (node (ref "U10") (pin "1") (pinfunction "PCKP_1") (pintype "unspecified"))
    )
    (net (code "244") (name "unconnected-(U11-GND-Pad1)") (class "Default")
      (node (ref "U11") (pin "1") (pinfunction "GND_1") (pintype "unspecified"))
    )
    (net (code "245") (name "unconnected-(U11-Vin-Pad3)") (class "Default")
      (node (ref "U11") (pin "3") (pinfunction "Vin_3") (pintype "unspecified"))
    )
    (net (code "246") (name "unconnected-(U11-Vout-Pad2)") (class "Default")
      (node (ref "U11") (pin "2") (pinfunction "Vout_2") (pintype "unspecified"))
    )
    (net (code "247") (name "unconnected-(U12-EN-Pad12)") (class "Default")
      (node (ref "U12") (pin "12") (pinfunction "EN_12") (pintype "unspecified"))
    )
    (net (code "248") (name "unconnected-(U12-FB-Pad3)") (class "Default")
      (node (ref "U12") (pin "3") (pinfunction "FB_3") (pintype "unspecified"))
    )
    (net (code "249") (name "unconnected-(U12-GND-Pad2)") (class "Default")
      (node (ref "U12") (pin "2") (pinfunction "GND_2") (pintype "unspecified"))
    )
    (net (code "250") (name "unconnected-(U12-L1-Pad8)") (class "Default")
      (node (ref "U12") (pin "8") (pinfunction "L1_8") (pintype "unspecified"))
    )
    (net (code "251") (name "unconnected-(U12-L1-Pad9)") (class "Default")
      (node (ref "U12") (pin "9") (pinfunction "L1_9") (pintype "unspecified"))
    )
    (net (code "252") (name "unconnected-(U12-L2-Pad6)") (class "Default")
      (node (ref "U12") (pin "6") (pinfunction "L2_6") (pintype "unspecified"))
    )
    (net (code "253") (name "unconnected-(U12-L2-Pad7)") (class "Default")
      (node (ref "U12") (pin "7") (pinfunction "L2_7") (pintype "unspecified"))
    )
    (net (code "254") (name "unconnected-(U12-PG-Pad14)") (class "Default")
      (node (ref "U12") (pin "14") (pinfunction "PG_14") (pintype "unspecified"))
    )
    (net (code "255") (name "unconnected-(U12-PGND-Pad15)") (class "Default")
      (node (ref "U12") (pin "15") (pinfunction "PGND_15") (pintype "unspecified"))
    )
    (net (code "256") (name "unconnected-(U12-PS{slash}SYNC-Pad13)") (class "Default")
      (node (ref "U12") (pin "13") (pinfunction "PS/SYNC_13") (pintype "unspecified"))
    )
    (net (code "257") (name "unconnected-(U12-VIN-Pad10)") (class "Default")
      (node (ref "U12") (pin "10") (pinfunction "VIN_10") (pintype "unspecified"))
    )
    (net (code "258") (name "unconnected-(U12-VIN-Pad11)") (class "Default")
      (node (ref "U12") (pin "11") (pinfunction "VIN_11") (pintype "unspecified"))
    )
    (net (code "259") (name "unconnected-(U12-VINA-Pad1)") (class "Default")
      (node (ref "U12") (pin "1") (pinfunction "VINA_1") (pintype "unspecified"))
    )
    (net (code "260") (name "unconnected-(U12-VOUT-Pad4)") (class "Default")
      (node (ref "U12") (pin "4") (pinfunction "VOUT_4") (pintype "unspecified"))
    )
    (net (code "261") (name "unconnected-(U12-VOUT-Pad5)") (class "Default")
      (node (ref "U12") (pin "5") (pinfunction "VOUT_5") (pintype "unspecified"))
    )
    (net (code "262") (name "unconnected-(U13-EN-Pad1)") (class "Default")
      (node (ref "U13") (pin "1") (pinfunction "EN_1") (pintype "unspecified"))
    )
    (net (code "263") (name "unconnected-(U13-FB-Pad5)") (class "Default")
      (node (ref "U13") (pin "5") (pinfunction "FB_5") (pintype "unspecified"))
    )
    (net (code "264") (name "unconnected-(U13-GND-Pad2)") (class "Default")
      (node (ref "U13") (pin "2") (pinfunction "GND_2") (pintype "unspecified"))
    )
    (net (code "265") (name "unconnected-(U13-IN-Pad4)") (class "Default")
      (node (ref "U13") (pin "4") (pinfunction "IN_4") (pintype "unspecified"))
    )
    (net (code "266") (name "unconnected-(U13-LX-Pad3)") (class "Default")
      (node (ref "U13") (pin "3") (pinfunction "LX_3") (pintype "unspecified"))
    )
    (net (code "267") (name "unconnected-(USB2-SBU1-PadA8)") (class "Default")
      (node (ref "USB2") (pin "A8") (pinfunction "SBU1_A8") (pintype "unspecified+no_connect"))
    )
    (net (code "268") (name "unconnected-(USB2-SBU2-PadB8)") (class "Default")
      (node (ref "USB2") (pin "B8") (pinfunction "SBU2_B8") (pintype "unspecified+no_connect"))
    )
    (net (code "269") (name "unconnected-(USB3-SBU1-PadA8)") (class "Default")
      (node (ref "USB3") (pin "A8") (pinfunction "SBU1_A8") (pintype "unspecified+no_connect"))
    )
    (net (code "270") (name "unconnected-(USB3-SBU2-PadB8)") (class "Default")
      (node (ref "USB3") (pin "B8") (pinfunction "SBU2_B8") (pintype "unspecified+no_connect"))
    )
    (net (code "271") (name "unconnected-(USB4-CC1-PadA5)") (class "Default")
      (node (ref "USB4") (pin "A5") (pinfunction "CC1_A5") (pintype "unspecified"))
    )
    (net (code "272") (name "unconnected-(USB4-CC2-PadB5)") (class "Default")
      (node (ref "USB4") (pin "B5") (pinfunction "CC2_B5") (pintype "unspecified"))
    )
    (net (code "273") (name "unconnected-(USB4-Dn1-PadA7)") (class "Default")
      (node (ref "USB4") (pin "A7") (pinfunction "Dn1_A7") (pintype "unspecified"))
    )
    (net (code "274") (name "unconnected-(USB4-Dn2-PadB7)") (class "Default")
      (node (ref "USB4") (pin "B7") (pinfunction "Dn2_B7") (pintype "unspecified"))
    )
    (net (code "275") (name "unconnected-(USB4-Dp1-PadA6)") (class "Default")
      (node (ref "USB4") (pin "A6") (pinfunction "Dp1_A6") (pintype "unspecified"))
    )
    (net (code "276") (name "unconnected-(USB4-Dp2-PadB6)") (class "Default")
      (node (ref "USB4") (pin "B6") (pinfunction "Dp2_B6") (pintype "unspecified"))
    )
    (net (code "277") (name "unconnected-(USB4-EH-Pad13)") (class "Default")
      (node (ref "USB4") (pin "13") (pinfunction "EH_13") (pintype "unspecified"))
    )
    (net (code "278") (name "unconnected-(USB4-EH-Pad14)") (class "Default")
      (node (ref "USB4") (pin "14") (pinfunction "EH_14") (pintype "unspecified"))
    )
    (net (code "279") (name "unconnected-(USB4-GND-PadA1B12)") (class "Default")
      (node (ref "USB4") (pin "A1B12") (pinfunction "GND_A1B12") (pintype "unspecified"))
    )
    (net (code "280") (name "unconnected-(USB4-GND-PadB1A12)") (class "Default")
      (node (ref "USB4") (pin "B1A12") (pinfunction "GND_B1A12") (pintype "unspecified"))
    )
    (net (code "281") (name "unconnected-(USB4-SBU1-PadA8)") (class "Default")
      (node (ref "USB4") (pin "A8") (pinfunction "SBU1_A8") (pintype "unspecified"))
    )
    (net (code "282") (name "unconnected-(USB4-SBU2-PadB8)") (class "Default")
      (node (ref "USB4") (pin "B8") (pinfunction "SBU2_B8") (pintype "unspecified"))
    )
    (net (code "283") (name "unconnected-(USB4-VBUS-PadA4B9)") (class "Default")
      (node (ref "USB4") (pin "A4B9") (pinfunction "VBUS_A4B9") (pintype "unspecified"))
    )
    (net (code "284") (name "unconnected-(USB4-VBUS-PadB4A9)") (class "Default")
      (node (ref "USB4") (pin "B4A9") (pinfunction "VBUS_B4A9") (pintype "unspecified"))
    )
  )
)
